# design.net
KiCad netlist of a schematic drawn in Altium Designer
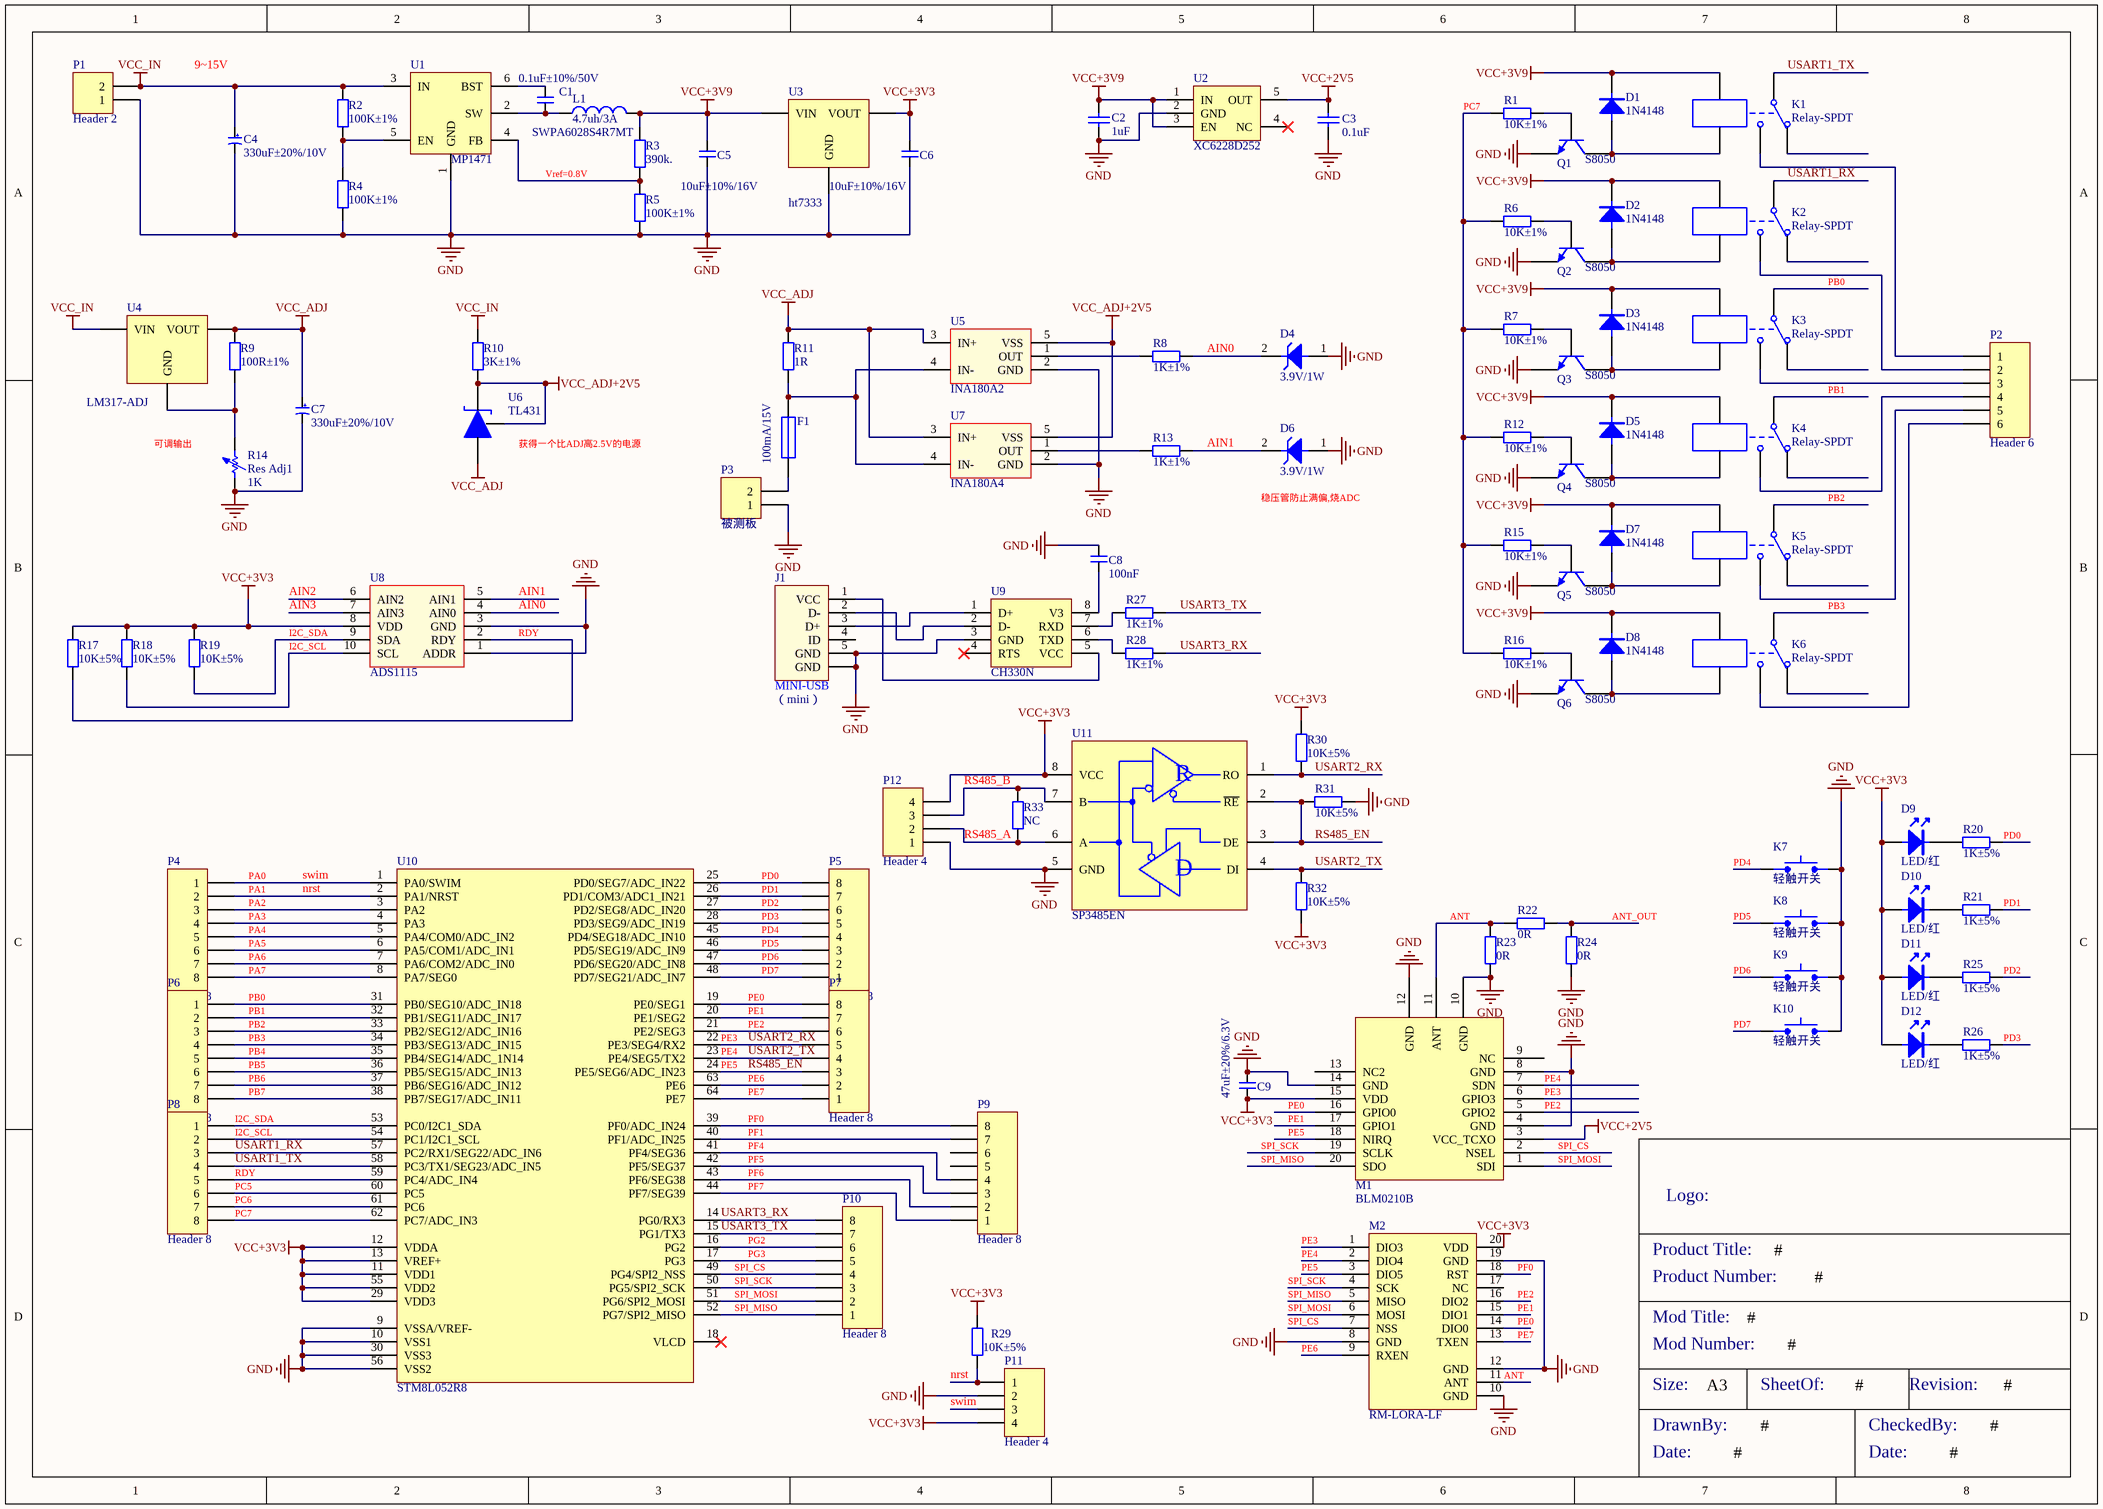
[diagram p0: 电流测试工装板.SchDoc]

(export (version "E")
  (design (tool "Eeschema 10.0.6"))
  (components
    (comp (ref "C1")
      (value "0.1uF±10%/50V")
      (footprint "c0402")
      (description "瓷片电容-0.1uF-±10%-16V-X5R-0402")
      (fields
        (field (name "PART NUMBER") "1.2.04.05.0169")
        (field (name "COMPONENTLINK1URL") "z:\\altiumdesigner\\规格书\\02原材料\\04电容\\05瓷片电容\\")
        (field (name "COMPONENTLINK2URL") "z:\\altiumdesigner\\规格书\\02原材料\\04电容\\05瓷片电容\\")
        (field (name "PUBLISHER") "徐永伟")
        (field (name "EDIT NOTE") "V1.0-创建-20161230-徐永伟")
      )
      (libsource (lib "檀木科技") (part "无极性电容"))
    )
    (comp (ref "C2")
      (value "1uF")
      (footprint "C0402")
      (description "Capacitor,Ceramic,0603-16V-X5R-104-K-YAGEO")
      (fields (field (name "MANUFACTURER") "YAGEO") (field (name "PUBLISHER") "Altium Limited"))
      (libsource (lib "*") (part "Cap"))
    )
    (comp (ref "C3")
      (value "0.1uF")
      (footprint "C0402")
      (description "Capacitor,Ceramic,0603-16V-X5R-104-K-YAGEO")
      (fields (field (name "MANUFACTURER") "YAGEO") (field (name "PUBLISHER") "Altium Limited"))
      (libsource (lib "*") (part "Cap"))
    )
    (comp (ref "C4")
      (value "330uF±20%/10V")
      (footprint "CAP_2P_2R5_D6R3H11_W")
      (description "电解电容_330uF±20%/10V_0.2R_-40~105℃_4000Hours_D6R3H11")
      (fields
        (field (name "PART NUMBER") "1.2.04.03.0001")
        (field (name "COMPONENTLINK1URL") "z:\\规格书\\02原材料\\04电容\\03铝电解电容\\常州超威电解电容RT系列.pdf")
        (field (name "PUBLISHER") "徐永伟")
        (field (name "EDIT NOTE") "V1.0-创建-20190329-徐永伟")
      )
      (libsource (lib "瑞臻信息") (part "极性电容"))
    )
    (comp (ref "C5")
      (value "10uF±10%/16V")
      (footprint "瑞臻信息:c0805")
      (description "瓷片电容-10uF-±10%-16V-X5R-0805")
      (fields
        (field (name "PART NUMBER") "1.2.04.05.0201")
        (field (name "COMPONENTLINK1URL") "z:\\altiumdesigner\\规格书\\02原材料\\04电容\\05瓷片电容\\")
        (field (name "COMPONENTLINK2URL") "z:\\altiumdesigner\\规格书\\02原材料\\04电容\\05瓷片电容\\")
        (field (name "PUBLISHER") "徐永伟")
        (field (name "EDIT NOTE") "V1.0-创建-20161230-徐永伟")
      )
      (libsource (lib "檀木科技") (part "无极性电容"))
    )
    (comp (ref "C6")
      (value "10uF±10%/16V")
      (footprint "瑞臻信息:c0805")
      (description "瓷片电容-10uF-±10%-16V-X5R-0805")
      (fields
        (field (name "PART NUMBER") "1.2.04.05.0201")
        (field (name "COMPONENTLINK1URL") "z:\\altiumdesigner\\规格书\\02原材料\\04电容\\05瓷片电容\\")
        (field (name "COMPONENTLINK2URL") "z:\\altiumdesigner\\规格书\\02原材料\\04电容\\05瓷片电容\\")
        (field (name "PUBLISHER") "徐永伟")
        (field (name "EDIT NOTE") "V1.0-创建-20161230-徐永伟")
      )
      (libsource (lib "檀木科技") (part "无极性电容"))
    )
    (comp (ref "C7")
      (value "330uF±20%/10V")
      (footprint "CAP_2P_2R5_D6R3H11_W")
      (description "电解电容_330uF±20%/10V_0.2R_-40~105℃_4000Hours_D6R3H11")
      (fields
        (field (name "PART NUMBER") "1.2.04.03.0001")
        (field (name "COMPONENTLINK1URL") "z:\\规格书\\02原材料\\04电容\\03铝电解电容\\常州超威电解电容RT系列.pdf")
        (field (name "PUBLISHER") "徐永伟")
        (field (name "EDIT NOTE") "V1.0-创建-20190329-徐永伟")
      )
      (libsource (lib "瑞臻信息") (part "极性电容"))
    )
    (comp (ref "C8")
      (value "100nF")
      (footprint "c0402")
      (description "MLCC_47uF±20%_6.3V_X5R_H1.6mm_1206")
      (fields
        (field (name "PART NUMBER") "1.2.04.05.0001")
        (field (name "COMPONENTLINK1URL") "z:\\规格书\\02原材料\\04电容\\05瓷片电容\\SAMS-S-A0000377162-1.pdf")
        (field (name "PUBLISHER") "徐永伟")
        (field (name "EDIT NOTE") "V1.0-创建-20180711-徐永伟")
      )
      (libsource (lib "瑞臻信息") (part "无极性电容"))
    )
    (comp (ref "C9")
      (value "47uF±20%/6.3V")
      (footprint "C1206")
      (description "MLCC_47uF±20%_6.3V_X5R_H1.6mm_1206")
      (fields
        (field (name "PART NUMBER") "1.2.04.05.0001")
        (field (name "COMPONENTLINK1URL") "z:\\规格书\\02原材料\\04电容\\05瓷片电容\\SAMS-S-A0000377162-1.pdf")
        (field (name "PUBLISHER") "徐永伟")
        (field (name "EDIT NOTE") "V1.0-创建-20180711-徐永伟")
      )
      (libsource (lib "瑞臻信息") (part "无极性电容"))
    )
    (comp (ref "D1")
      (value "1N4148")
      (footprint "SOD123_2P_1R6X2R7")
      (description "开关二极管_1N4148_0.3A/100V_Vf=0.5V_SOD123")
      (fields
        (field (name "PART NUMBER") "1.2.08.01.0002")
        (field (name "COMPONENTLINK1URL") "Z:\\规格书\\02原材料\\08晶体管\\01二极管\\1N4148SOD123.PDF")
        (field (name "PUBLISHER") "徐永伟")
        (field (name "EDIT NOTE") "V1.0-创建-20190815-徐永伟")
      )
      (libsource (lib "瑞臻信息") (part "普通二极管"))
    )
    (comp (ref "D2")
      (value "1N4148")
      (footprint "SOD123_2P_1R6X2R7")
      (description "开关二极管_1N4148_0.3A/100V_Vf=0.5V_SOD123")
      (fields
        (field (name "PART NUMBER") "1.2.08.01.0002")
        (field (name "COMPONENTLINK1URL") "Z:\\规格书\\02原材料\\08晶体管\\01二极管\\1N4148SOD123.PDF")
        (field (name "PUBLISHER") "徐永伟")
        (field (name "EDIT NOTE") "V1.0-创建-20190815-徐永伟")
      )
      (libsource (lib "瑞臻信息") (part "普通二极管"))
    )
    (comp (ref "D3")
      (value "1N4148")
      (footprint "SOD123_2P_1R6X2R7")
      (description "开关二极管_1N4148_0.3A/100V_Vf=0.5V_SOD123")
      (fields
        (field (name "PART NUMBER") "1.2.08.01.0002")
        (field (name "COMPONENTLINK1URL") "Z:\\规格书\\02原材料\\08晶体管\\01二极管\\1N4148SOD123.PDF")
        (field (name "PUBLISHER") "徐永伟")
        (field (name "EDIT NOTE") "V1.0-创建-20190815-徐永伟")
      )
      (libsource (lib "瑞臻信息") (part "普通二极管"))
    )
    (comp (ref "D4")
      (value "3.9V/1W")
      (footprint "LL41_2P_D2R5H5R0")
      (description "稳压二极管_ZM4730A_3.9V/1W_LL41")
      (fields
        (field (name "PART NUMBER") "1.2.08.04.0001")
        (field (name "COMPONENTLINK1URL") "Z:\\规格书\\02原材料\\08晶体管\\04稳压二极管\\ZM4730A.pdf")
        (field (name "PUBLISHER") "徐永伟")
        (field (name "EDIT NOTE") "V1.0-创建-20190815-徐永伟")
      )
      (libsource (lib "瑞臻信息") (part "齐纳二极管"))
    )
    (comp (ref "D5")
      (value "1N4148")
      (footprint "SOD123_2P_1R6X2R7")
      (description "开关二极管_1N4148_0.3A/100V_Vf=0.5V_SOD123")
      (fields
        (field (name "PART NUMBER") "1.2.08.01.0002")
        (field (name "COMPONENTLINK1URL") "Z:\\规格书\\02原材料\\08晶体管\\01二极管\\1N4148SOD123.PDF")
        (field (name "PUBLISHER") "徐永伟")
        (field (name "EDIT NOTE") "V1.0-创建-20190815-徐永伟")
      )
      (libsource (lib "瑞臻信息") (part "普通二极管"))
    )
    (comp (ref "D6")
      (value "3.9V/1W")
      (footprint "LL41_2P_D2R5H5R0")
      (description "稳压二极管_ZM4730A_3.9V/1W_LL41")
      (fields
        (field (name "PART NUMBER") "1.2.08.04.0001")
        (field (name "COMPONENTLINK1URL") "Z:\\规格书\\02原材料\\08晶体管\\04稳压二极管\\ZM4730A.pdf")
        (field (name "PUBLISHER") "徐永伟")
        (field (name "EDIT NOTE") "V1.0-创建-20190815-徐永伟")
      )
      (libsource (lib "瑞臻信息") (part "齐纳二极管"))
    )
    (comp (ref "D7")
      (value "1N4148")
      (footprint "SOD123_2P_1R6X2R7")
      (description "开关二极管_1N4148_0.3A/100V_Vf=0.5V_SOD123")
      (fields
        (field (name "PART NUMBER") "1.2.08.01.0002")
        (field (name "COMPONENTLINK1URL") "Z:\\规格书\\02原材料\\08晶体管\\01二极管\\1N4148SOD123.PDF")
        (field (name "PUBLISHER") "徐永伟")
        (field (name "EDIT NOTE") "V1.0-创建-20190815-徐永伟")
      )
      (libsource (lib "瑞臻信息") (part "普通二极管"))
    )
    (comp (ref "D8")
      (value "1N4148")
      (footprint "SOD123_2P_1R6X2R7")
      (description "开关二极管_1N4148_0.3A/100V_Vf=0.5V_SOD123")
      (fields
        (field (name "PART NUMBER") "1.2.08.01.0002")
        (field (name "COMPONENTLINK1URL") "Z:\\规格书\\02原材料\\08晶体管\\01二极管\\1N4148SOD123.PDF")
        (field (name "PUBLISHER") "徐永伟")
        (field (name "EDIT NOTE") "V1.0-创建-20190815-徐永伟")
      )
      (libsource (lib "瑞臻信息") (part "普通二极管"))
    )
    (comp (ref "D9")
      (value "LED/红")
      (footprint "PZ_1X2P_2R54_Z")
      (description "发光二极管_红色_Vf=2.3V_0603")
      (fields
        (field (name "PART NUMBER") "1.2.08.02.0002")
        (field (name "COMPONENTLINK1URL") "Z:\\规格书\\02原材料\\08晶体管\\02发光二极管\\E6C0603URAC1UDA(630nm).pdf")
        (field (name "PUBLISHER") "徐永伟")
        (field (name "EDIT NOTE") "V1.0-创建-20190815-徐永伟")
      )
      (libsource (lib "瑞臻信息") (part "单LED"))
    )
    (comp (ref "D10")
      (value "LED/红")
      (footprint "PZ_1X2P_2R54_Z")
      (description "发光二极管_红色_Vf=2.3V_0603")
      (fields
        (field (name "PART NUMBER") "1.2.08.02.0002")
        (field (name "COMPONENTLINK1URL") "Z:\\规格书\\02原材料\\08晶体管\\02发光二极管\\E6C0603URAC1UDA(630nm).pdf")
        (field (name "PUBLISHER") "徐永伟")
        (field (name "EDIT NOTE") "V1.0-创建-20190815-徐永伟")
      )
      (libsource (lib "瑞臻信息") (part "单LED"))
    )
    (comp (ref "D11")
      (value "LED/红")
      (footprint "PZ_1X2P_2R54_Z")
      (description "发光二极管_红色_Vf=2.3V_0603")
      (fields
        (field (name "PART NUMBER") "1.2.08.02.0002")
        (field (name "COMPONENTLINK1URL") "Z:\\规格书\\02原材料\\08晶体管\\02发光二极管\\E6C0603URAC1UDA(630nm).pdf")
        (field (name "PUBLISHER") "徐永伟")
        (field (name "EDIT NOTE") "V1.0-创建-20190815-徐永伟")
      )
      (libsource (lib "瑞臻信息") (part "单LED"))
    )
    (comp (ref "D12")
      (value "LED/红")
      (footprint "PZ_1X2P_2R54_Z")
      (description "发光二极管_红色_Vf=2.3V_0603")
      (fields
        (field (name "PART NUMBER") "1.2.08.02.0002")
        (field (name "COMPONENTLINK1URL") "Z:\\规格书\\02原材料\\08晶体管\\02发光二极管\\E6C0603URAC1UDA(630nm).pdf")
        (field (name "PUBLISHER") "徐永伟")
        (field (name "EDIT NOTE") "V1.0-创建-20190815-徐永伟")
      )
      (libsource (lib "瑞臻信息") (part "单LED"))
    )
    (comp (ref "F1")
      (value "100mA/15V")
      (footprint "FUSE0603")
      (description "自恢复保险丝_0.05A/15V_100A_0.5W_0.5A/1.5s_0603")
      (fields
        (field (name "PART NUMBER") "1.2.13.03.0001")
        (field (name "COMPONENTLINK1URL") "Z:\\规格书\\02原材料\\13保护器件\\03自恢复保险丝\\0.05APTC.PDF")
        (field (name "PUBLISHER") "徐永伟")
        (field (name "EDIT NOTE") "V1.0-创建-20190816-徐永伟")
      )
      (libsource (lib "瑞臻信息") (part "保险丝"))
    )
    (comp (ref "J1")
      (value "（mini）")
      (footprint "DIP_MINI_USB-1")
      (libsource (lib "瑞臻信息") (part "USB座子-2（mini）"))
    )
    (comp (ref "K1")
      (value "Relay-SPDT")
      (footprint "SRS-XXVDC-SL")
      (description "Single-Pole Dual-Throw Relay")
      (fields (field (name "PUBLISHER") "Altium Limited"))
      (libsource (lib "Miscellaneous Devices") (part "Relay-SPDT"))
    )
    (comp (ref "K2")
      (value "Relay-SPDT")
      (footprint "SRS-XXVDC-SL")
      (description "Single-Pole Dual-Throw Relay")
      (fields (field (name "PUBLISHER") "Altium Limited"))
      (libsource (lib "Miscellaneous Devices") (part "Relay-SPDT"))
    )
    (comp (ref "K3")
      (value "Relay-SPDT")
      (footprint "SRS-XXVDC-SL")
      (description "Single-Pole Dual-Throw Relay")
      (fields (field (name "PUBLISHER") "Altium Limited"))
      (libsource (lib "Miscellaneous Devices") (part "Relay-SPDT"))
    )
    (comp (ref "K4")
      (value "Relay-SPDT")
      (footprint "SRS-XXVDC-SL")
      (description "Single-Pole Dual-Throw Relay")
      (fields (field (name "PUBLISHER") "Altium Limited"))
      (libsource (lib "Miscellaneous Devices") (part "Relay-SPDT"))
    )
    (comp (ref "K5")
      (value "Relay-SPDT")
      (footprint "SRS-XXVDC-SL")
      (description "Single-Pole Dual-Throw Relay")
      (fields (field (name "PUBLISHER") "Altium Limited"))
      (libsource (lib "Miscellaneous Devices") (part "Relay-SPDT"))
    )
    (comp (ref "K6")
      (value "Relay-SPDT")
      (footprint "SRS-XXVDC-SL")
      (description "Single-Pole Dual-Throw Relay")
      (fields (field (name "PUBLISHER") "Altium Limited"))
      (libsource (lib "Miscellaneous Devices") (part "Relay-SPDT"))
    )
    (comp (ref "K7")
      (value "轻触开关")
      (footprint "PZ_1X2P_2R54_Z")
      (description "轻触开关_12Vdc/50mA_0.25mm_250gf_3.6X6.1X2.5mm_表贴SMD")
      (fields
        (field (name "PART NUMBER") "1.2.15.01.0001")
        (field (name "COMPONENTLINK1URL") "Z:\\规格书\\02原材料\\15机械开关\\01轻触按钮开关\\C118141.pdf")
        (field (name "PUBLISHER") "徐永伟")
        (field (name "EDIT NOTE") "V1.0-创建-20190825-徐永伟")
      )
      (libsource (lib "瑞臻信息") (part "2脚按键-1"))
    )
    (comp (ref "K8")
      (value "轻触开关")
      (footprint "PZ_1X2P_2R54_Z")
      (description "轻触开关_12Vdc/50mA_0.25mm_250gf_3.6X6.1X2.5mm_表贴SMD")
      (fields
        (field (name "PART NUMBER") "1.2.15.01.0001")
        (field (name "COMPONENTLINK1URL") "Z:\\规格书\\02原材料\\15机械开关\\01轻触按钮开关\\C118141.pdf")
        (field (name "PUBLISHER") "徐永伟")
        (field (name "EDIT NOTE") "V1.0-创建-20190825-徐永伟")
      )
      (libsource (lib "瑞臻信息") (part "2脚按键-1"))
    )
    (comp (ref "K9")
      (value "轻触开关")
      (footprint "PZ_1X2P_2R54_Z")
      (description "轻触开关_12Vdc/50mA_0.25mm_250gf_3.6X6.1X2.5mm_表贴SMD")
      (fields
        (field (name "PART NUMBER") "1.2.15.01.0001")
        (field (name "COMPONENTLINK1URL") "Z:\\规格书\\02原材料\\15机械开关\\01轻触按钮开关\\C118141.pdf")
        (field (name "PUBLISHER") "徐永伟")
        (field (name "EDIT NOTE") "V1.0-创建-20190825-徐永伟")
      )
      (libsource (lib "瑞臻信息") (part "2脚按键-1"))
    )
    (comp (ref "K10")
      (value "轻触开关")
      (footprint "PZ_1X2P_2R54_Z")
      (description "轻触开关_12Vdc/50mA_0.25mm_250gf_3.6X6.1X2.5mm_表贴SMD")
      (fields
        (field (name "PART NUMBER") "1.2.15.01.0001")
        (field (name "COMPONENTLINK1URL") "Z:\\规格书\\02原材料\\15机械开关\\01轻触按钮开关\\C118141.pdf")
        (field (name "PUBLISHER") "徐永伟")
        (field (name "EDIT NOTE") "V1.0-创建-20190825-徐永伟")
      )
      (libsource (lib "瑞臻信息") (part "2脚按键-1"))
    )
    (comp (ref "L1")
      (value "SWPA6028S4R7MT")
      (footprint "SMD_INC_2P_6R0X6R0")
      (description "Inductor")
      (fields (field (name "ALTIUM_VALUE") "4.7uh/3A"))
      (libsource (lib "Miscellaneous Devices") (part "Inductor"))
    )
    (comp (ref "M1")
      (value "BLM0210B")
      (footprint "FskMode_BL")
      (description "SI4463模块，不带LNA")
      (fields
        (field (name "PART NUMBER") "1.1.01.38.0002")
        (field (name "COMPONENTLINK1URL") "Z:\\规格书\\02原材料\\21电路模块\\04无线模块\\4463模块资料.rar")
        (field (name "PUBLISHER") "徐永伟")
        (field (name "EDIT NOTE") "V1.0-创建-20180709-徐永伟")
      )
      (libsource (lib "瑞臻信息") (part "SI4463_Module"))
    )
    (comp (ref "M2")
      (value "RM-LORA-LF")
      (footprint "LORA_PIN_1")
      (description "LORA模块_RM-LORA-PCB11-V2.21_430M~490M_Pout=17dBm_SMD20")
      (fields
        (field (name "PART NUMBER") "1.1.01.38.0003")
        (field (name "COMPONENTLINK1URL") "Z:\\规格书\\02原材料\\21电路模块\\04无线模块\\")
        (field (name "PUBLISHER") "徐永伟")
        (field (name "EDIT NOTE") "V1.0-创建-20180709-徐永伟")
      )
      (libsource (lib "瑞臻信息") (part "LORA_PIN_1"))
    )
    (comp (ref "P1")
      (value "Header 2")
      (footprint "HDR1X2")
      (description "Header, 2-Pin")
      (fields (field (name "PUBLISHER") "Altium Limited"))
      (libsource (lib "Miscellaneous Connectors") (part "Header 2"))
    )
    (comp (ref "P2")
      (value "Header 6")
      (footprint "HDR1X6")
      (description "Header, 6-Pin")
      (fields (field (name "PUBLISHER") "Altium Limited"))
      (libsource (lib "Miscellaneous Connectors") (part "Header 6"))
    )
    (comp (ref "P3")
      (value "被测板")
      (footprint "HDR1X2")
      (description "Header, 2-Pin")
      (fields (field (name "PUBLISHER") "Altium Limited"))
      (libsource (lib "Miscellaneous Connectors") (part "Header 2"))
    )
    (comp (ref "P4")
      (value "Header 8")
      (footprint "HDR1X8")
      (description "Header, 8-Pin")
      (fields (field (name "PUBLISHER") "Altium Limited"))
      (libsource (lib "") (part "Header 8_1"))
    )
    (comp (ref "P5")
      (value "Header 8")
      (footprint "HDR1X8")
      (description "Header, 8-Pin")
      (fields (field (name "PUBLISHER") "Altium Limited"))
      (libsource (lib "Miscellaneous Connectors") (part "Header 8"))
    )
    (comp (ref "P6")
      (value "Header 8")
      (footprint "HDR1X8")
      (description "Header, 8-Pin")
      (fields (field (name "PUBLISHER") "Altium Limited"))
      (libsource (lib "") (part "Header 8_1"))
    )
    (comp (ref "P7")
      (value "Header 8")
      (footprint "HDR1X8")
      (description "Header, 8-Pin")
      (fields (field (name "PUBLISHER") "Altium Limited"))
      (libsource (lib "Miscellaneous Connectors") (part "Header 8"))
    )
    (comp (ref "P8")
      (value "Header 8")
      (footprint "HDR1X8")
      (description "Header, 8-Pin")
      (fields (field (name "PUBLISHER") "Altium Limited"))
      (libsource (lib "") (part "Header 8_1"))
    )
    (comp (ref "P9")
      (value "Header 8")
      (footprint "HDR1X8")
      (description "Header, 8-Pin")
      (fields (field (name "PUBLISHER") "Altium Limited"))
      (libsource (lib "Miscellaneous Connectors") (part "Header 8"))
    )
    (comp (ref "P10")
      (value "Header 8")
      (footprint "HDR1X8")
      (description "Header, 8-Pin")
      (fields (field (name "PUBLISHER") "Altium Limited"))
      (libsource (lib "Miscellaneous Connectors") (part "Header 8"))
    )
    (comp (ref "P11")
      (value "Header 4")
      (footprint "HDR1X4")
      (description "Header, 4-Pin")
      (fields (field (name "PUBLISHER") "Altium Limited"))
      (libsource (lib "") (part "Header 4_1"))
    )
    (comp (ref "P12")
      (value "Header 4")
      (footprint "HDR1X4")
      (description "Header, 4-Pin")
      (fields (field (name "PUBLISHER") "Altium Limited"))
      (libsource (lib "Miscellaneous Connectors") (part "Header 4"))
    )
    (comp (ref "Q1")
      (value "S8050")
      (footprint "SOT23_3P_0R95_1R3X2R9")
      (description "三极管	_NPN_S8050_Vceo=25V_Ic=0.5A_β>50_SOT23")
      (fields
        (field (name "PART NUMBER") "1.2.08.08.0002")
        (field (name "COMPONENTLINK1URL") "Z:\\规格书\\02原材料\\08晶体管\\08三极管\\S8050_SOT23.pdf")
        (field (name "PUBLISHER") "徐永伟")
        (field (name "EDIT NOTE") "V1.0-创建-20190815-徐永伟")
      )
      (libsource (lib "瑞臻信息") (part "NPN三极管"))
    )
    (comp (ref "Q2")
      (value "S8050")
      (footprint "SOT23_3P_0R95_1R3X2R9")
      (description "三极管	_NPN_S8050_Vceo=25V_Ic=0.5A_β>50_SOT23")
      (fields
        (field (name "PART NUMBER") "1.2.08.08.0002")
        (field (name "COMPONENTLINK1URL") "Z:\\规格书\\02原材料\\08晶体管\\08三极管\\S8050_SOT23.pdf")
        (field (name "PUBLISHER") "徐永伟")
        (field (name "EDIT NOTE") "V1.0-创建-20190815-徐永伟")
      )
      (libsource (lib "瑞臻信息") (part "NPN三极管"))
    )
    (comp (ref "Q3")
      (value "S8050")
      (footprint "SOT23_3P_0R95_1R3X2R9")
      (description "三极管	_NPN_S8050_Vceo=25V_Ic=0.5A_β>50_SOT23")
      (fields
        (field (name "PART NUMBER") "1.2.08.08.0002")
        (field (name "COMPONENTLINK1URL") "Z:\\规格书\\02原材料\\08晶体管\\08三极管\\S8050_SOT23.pdf")
        (field (name "PUBLISHER") "徐永伟")
        (field (name "EDIT NOTE") "V1.0-创建-20190815-徐永伟")
      )
      (libsource (lib "瑞臻信息") (part "NPN三极管"))
    )
    (comp (ref "Q4")
      (value "S8050")
      (footprint "SOT23_3P_0R95_1R3X2R9")
      (description "三极管	_NPN_S8050_Vceo=25V_Ic=0.5A_β>50_SOT23")
      (fields
        (field (name "PART NUMBER") "1.2.08.08.0002")
        (field (name "COMPONENTLINK1URL") "Z:\\规格书\\02原材料\\08晶体管\\08三极管\\S8050_SOT23.pdf")
        (field (name "PUBLISHER") "徐永伟")
        (field (name "EDIT NOTE") "V1.0-创建-20190815-徐永伟")
      )
      (libsource (lib "瑞臻信息") (part "NPN三极管"))
    )
    (comp (ref "Q5")
      (value "S8050")
      (footprint "SOT23_3P_0R95_1R3X2R9")
      (description "三极管	_NPN_S8050_Vceo=25V_Ic=0.5A_β>50_SOT23")
      (fields
        (field (name "PART NUMBER") "1.2.08.08.0002")
        (field (name "COMPONENTLINK1URL") "Z:\\规格书\\02原材料\\08晶体管\\08三极管\\S8050_SOT23.pdf")
        (field (name "PUBLISHER") "徐永伟")
        (field (name "EDIT NOTE") "V1.0-创建-20190815-徐永伟")
      )
      (libsource (lib "瑞臻信息") (part "NPN三极管"))
    )
    (comp (ref "Q6")
      (value "S8050")
      (footprint "SOT23_3P_0R95_1R3X2R9")
      (description "三极管	_NPN_S8050_Vceo=25V_Ic=0.5A_β>50_SOT23")
      (fields
        (field (name "PART NUMBER") "1.2.08.08.0002")
        (field (name "COMPONENTLINK1URL") "Z:\\规格书\\02原材料\\08晶体管\\08三极管\\S8050_SOT23.pdf")
        (field (name "PUBLISHER") "徐永伟")
        (field (name "EDIT NOTE") "V1.0-创建-20190815-徐永伟")
      )
      (libsource (lib "瑞臻信息") (part "NPN三极管"))
    )
    (comp (ref "R1")
      (value "10K±1%")
      (footprint "R0603")
      (description "电阻_10K±1%_1/10W_0603")
      (fields
        (field (name "PART NUMBER") "1.2.03.01.0009")
        (field (name "COMPONENTLINK1URL") "z:\\规格书\\02原材料\\03电阻\\01普通电阻\\旺诠电阻.pdf")
        (field (name "创建者") "徐永伟")
      )
      (libsource (lib "瑞臻信息") (part "普通电阻"))
    )
    (comp (ref "R2")
      (value "100K±1%")
      (footprint "R0402")
      (description "贴片电阻，1K±5%，1/16W，50V，0402")
      (fields
        (field (name "PART NUMBER") "1.2.03.01.XXX1")
        (field (name "PUBLISHER") "徐永伟")
        (field (name "EDIT NOTE") "V1.0-创建-20160831-徐永伟")
      )
      (libsource (lib "檀木科技") (part "普通电阻"))
    )
    (comp (ref "R3")
      (value "390k.")
      (footprint "R0402")
      (description "电阻_510R±1%_1/16W_0402")
      (fields
        (field (name "PART NUMBER") "1.2.03.01.0019")
        (field (name "COMPONENTLINK1URL") "z:\\规格书\\02原材料\\03电阻\\01普通电阻\\厚声电阻.pdf")
        (field (name "创建者") "徐永伟")
      )
      (libsource (lib "") (part "普通电阻_1"))
    )
    (comp (ref "R4")
      (value "100K±1%")
      (footprint "R0402")
      (description "贴片电阻，1K±5%，1/16W，50V，0402")
      (fields
        (field (name "PART NUMBER") "1.2.03.01.XXX1")
        (field (name "PUBLISHER") "徐永伟")
        (field (name "EDIT NOTE") "V1.0-创建-20160831-徐永伟")
      )
      (libsource (lib "檀木科技") (part "普通电阻"))
    )
    (comp (ref "R5")
      (value "100K±1%")
      (footprint "R0402")
      (description "贴片电阻，1K±5%，1/16W，50V，0402")
      (fields
        (field (name "PART NUMBER") "1.2.03.01.XXX1")
        (field (name "PUBLISHER") "徐永伟")
        (field (name "EDIT NOTE") "V1.0-创建-20160831-徐永伟")
      )
      (libsource (lib "檀木科技") (part "普通电阻"))
    )
    (comp (ref "R6")
      (value "10K±1%")
      (footprint "R0603")
      (description "电阻_10K±1%_1/10W_0603")
      (fields
        (field (name "PART NUMBER") "1.2.03.01.0009")
        (field (name "COMPONENTLINK1URL") "z:\\规格书\\02原材料\\03电阻\\01普通电阻\\旺诠电阻.pdf")
        (field (name "创建者") "徐永伟")
      )
      (libsource (lib "瑞臻信息") (part "普通电阻"))
    )
    (comp (ref "R7")
      (value "10K±1%")
      (footprint "R0603")
      (description "电阻_10K±1%_1/10W_0603")
      (fields
        (field (name "PART NUMBER") "1.2.03.01.0009")
        (field (name "COMPONENTLINK1URL") "z:\\规格书\\02原材料\\03电阻\\01普通电阻\\旺诠电阻.pdf")
        (field (name "创建者") "徐永伟")
      )
      (libsource (lib "瑞臻信息") (part "普通电阻"))
    )
    (comp (ref "R8")
      (value "1K±1%")
      (footprint "R0603")
      (description "电阻_1K±1%_1/10W_0603")
      (fields
        (field (name "PART NUMBER") "1.2.03.01.0006")
        (field (name "COMPONENTLINK1URL") "z:\\规格书\\02原材料\\03电阻\\01普通电阻\\旺诠电阻.pdf")
        (field (name "创建者") "徐永伟")
      )
      (libsource (lib "瑞臻信息") (part "普通电阻"))
    )
    (comp (ref "R9")
      (value "100R±1%")
      (footprint "R0603")
      (description "电阻_100R±1%_1/10W_0603")
      (fields
        (field (name "PART NUMBER") "1.2.03.01.0017")
        (field (name "COMPONENTLINK1URL") "z:\\规格书\\02原材料\\03电阻\\01普通电阻\\华科电阻.pdf")
        (field (name "创建者") "徐永伟")
      )
      (libsource (lib "") (part "普通电阻_1"))
    )
    (comp (ref "R10")
      (value "3K±1%")
      (footprint "R0603")
      (description "电阻_3K±1%_1/10W_0603")
      (fields
        (field (name "PART NUMBER") "1.2.03.01.0027")
        (field (name "COMPONENTLINK1URL") "z:\\规格书\\02原材料\\03电阻\\01普通电阻\\国巨电阻.pdf")
        (field (name "创建者") "徐永伟")
      )
      (libsource (lib "") (part "普通电阻_1"))
    )
    (comp (ref "R11")
      (value "1R")
      (footprint "R0603")
      (description "电阻_3K±1%_1/10W_0603")
      (fields
        (field (name "PART NUMBER") "1.2.03.01.0027")
        (field (name "COMPONENTLINK1URL") "z:\\规格书\\02原材料\\03电阻\\01普通电阻\\国巨电阻.pdf")
        (field (name "创建者") "徐永伟")
      )
      (libsource (lib "") (part "普通电阻_1"))
    )
    (comp (ref "R12")
      (value "10K±1%")
      (footprint "R0603")
      (description "电阻_10K±1%_1/10W_0603")
      (fields
        (field (name "PART NUMBER") "1.2.03.01.0009")
        (field (name "COMPONENTLINK1URL") "z:\\规格书\\02原材料\\03电阻\\01普通电阻\\旺诠电阻.pdf")
        (field (name "创建者") "徐永伟")
      )
      (libsource (lib "瑞臻信息") (part "普通电阻"))
    )
    (comp (ref "R13")
      (value "1K±1%")
      (footprint "R0603")
      (description "电阻_1K±1%_1/10W_0603")
      (fields
        (field (name "PART NUMBER") "1.2.03.01.0006")
        (field (name "COMPONENTLINK1URL") "z:\\规格书\\02原材料\\03电阻\\01普通电阻\\旺诠电阻.pdf")
        (field (name "创建者") "徐永伟")
      )
      (libsource (lib "瑞臻信息") (part "普通电阻"))
    )
    (comp (ref "R14")
      (value "Res Adj1")
      (footprint "AXIAL-0.7")
      (description "Variable Resistor")
      (fields (field (name "ALTIUM_VALUE") "1K") (field (name "PUBLISHER") "Altium Limited"))
      (libsource (lib "Miscellaneous Devices") (part "Res Adj1"))
    )
    (comp (ref "R15")
      (value "10K±1%")
      (footprint "R0603")
      (description "电阻_10K±1%_1/10W_0603")
      (fields
        (field (name "PART NUMBER") "1.2.03.01.0009")
        (field (name "COMPONENTLINK1URL") "z:\\规格书\\02原材料\\03电阻\\01普通电阻\\旺诠电阻.pdf")
        (field (name "创建者") "徐永伟")
      )
      (libsource (lib "瑞臻信息") (part "普通电阻"))
    )
    (comp (ref "R16")
      (value "10K±1%")
      (footprint "R0603")
      (description "电阻_10K±1%_1/10W_0603")
      (fields
        (field (name "PART NUMBER") "1.2.03.01.0009")
        (field (name "COMPONENTLINK1URL") "z:\\规格书\\02原材料\\03电阻\\01普通电阻\\旺诠电阻.pdf")
        (field (name "创建者") "徐永伟")
      )
      (libsource (lib "瑞臻信息") (part "普通电阻"))
    )
    (comp (ref "R17")
      (value "10K±5%")
      (footprint "R0402")
      (description "电阻_10K±5%_1/16W_0402")
      (fields
        (field (name "PART NUMBER") "1.2.03.01.0012")
        (field (name "COMPONENTLINK1URL") "z:\\规格书\\02原材料\\03电阻\\01普通电阻\\旺诠电阻.pdf")
        (field (name "创建者") "徐永伟")
      )
      (libsource (lib "") (part "普通电阻_1"))
    )
    (comp (ref "R18")
      (value "10K±5%")
      (footprint "R0402")
      (description "电阻_10K±5%_1/16W_0402")
      (fields
        (field (name "PART NUMBER") "1.2.03.01.0012")
        (field (name "COMPONENTLINK1URL") "z:\\规格书\\02原材料\\03电阻\\01普通电阻\\旺诠电阻.pdf")
        (field (name "创建者") "徐永伟")
      )
      (libsource (lib "") (part "普通电阻_1"))
    )
    (comp (ref "R19")
      (value "10K±5%")
      (footprint "R0402")
      (description "电阻_10K±5%_1/16W_0402")
      (fields
        (field (name "PART NUMBER") "1.2.03.01.0012")
        (field (name "COMPONENTLINK1URL") "z:\\规格书\\02原材料\\03电阻\\01普通电阻\\旺诠电阻.pdf")
        (field (name "创建者") "徐永伟")
      )
      (libsource (lib "") (part "普通电阻_1"))
    )
    (comp (ref "R20")
      (value "1K±5%")
      (footprint "R0402")
      (description "电阻_1K±5%_1/16W_0402")
      (fields
        (field (name "PART NUMBER") "1.2.03.01.0014")
        (field (name "COMPONENTLINK1URL") "z:\\规格书\\02原材料\\03电阻\\01普通电阻\\旺诠电阻.pdf")
        (field (name "创建者") "徐永伟")
      )
      (libsource (lib "瑞臻信息") (part "普通电阻"))
    )
    (comp (ref "R21")
      (value "1K±5%")
      (footprint "R0402")
      (description "电阻_1K±5%_1/16W_0402")
      (fields
        (field (name "PART NUMBER") "1.2.03.01.0014")
        (field (name "COMPONENTLINK1URL") "z:\\规格书\\02原材料\\03电阻\\01普通电阻\\旺诠电阻.pdf")
        (field (name "创建者") "徐永伟")
      )
      (libsource (lib "瑞臻信息") (part "普通电阻"))
    )
    (comp (ref "R22")
      (value "0R")
      (footprint "R0603")
      (description "电阻_10K±1%_1/10W_0603")
      (fields
        (field (name "PART NUMBER") "1.2.03.01.0009")
        (field (name "COMPONENTLINK1URL") "z:\\规格书\\02原材料\\03电阻\\01普通电阻\\旺诠电阻.pdf")
        (field (name "创建者") "徐永伟")
      )
      (libsource (lib "瑞臻信息") (part "普通电阻"))
    )
    (comp (ref "R23")
      (value "0R")
      (footprint "R0603")
      (description "电阻_10K±1%_1/10W_0603")
      (fields
        (field (name "PART NUMBER") "1.2.03.01.0009")
        (field (name "COMPONENTLINK1URL") "z:\\规格书\\02原材料\\03电阻\\01普通电阻\\旺诠电阻.pdf")
        (field (name "创建者") "徐永伟")
      )
      (libsource (lib "") (part "普通电阻_1"))
    )
    (comp (ref "R24")
      (value "0R")
      (footprint "R0603")
      (description "电阻_10K±1%_1/10W_0603")
      (fields
        (field (name "PART NUMBER") "1.2.03.01.0009")
        (field (name "COMPONENTLINK1URL") "z:\\规格书\\02原材料\\03电阻\\01普通电阻\\旺诠电阻.pdf")
        (field (name "创建者") "徐永伟")
      )
      (libsource (lib "") (part "普通电阻_1"))
    )
    (comp (ref "R25")
      (value "1K±5%")
      (footprint "R0402")
      (description "电阻_1K±5%_1/16W_0402")
      (fields
        (field (name "PART NUMBER") "1.2.03.01.0014")
        (field (name "COMPONENTLINK1URL") "z:\\规格书\\02原材料\\03电阻\\01普通电阻\\旺诠电阻.pdf")
        (field (name "创建者") "徐永伟")
      )
      (libsource (lib "瑞臻信息") (part "普通电阻"))
    )
    (comp (ref "R26")
      (value "1K±5%")
      (footprint "R0402")
      (description "电阻_1K±5%_1/16W_0402")
      (fields
        (field (name "PART NUMBER") "1.2.03.01.0014")
        (field (name "COMPONENTLINK1URL") "z:\\规格书\\02原材料\\03电阻\\01普通电阻\\旺诠电阻.pdf")
        (field (name "创建者") "徐永伟")
      )
      (libsource (lib "瑞臻信息") (part "普通电阻"))
    )
    (comp (ref "R27")
      (value "1K±1%")
      (footprint "R0603")
      (description "电阻_1K±1%_1/10W_0603")
      (fields
        (field (name "PART NUMBER") "1.2.03.01.0006")
        (field (name "COMPONENTLINK1URL") "z:\\规格书\\02原材料\\03电阻\\01普通电阻\\旺诠电阻.pdf")
        (field (name "创建者") "徐永伟")
      )
      (libsource (lib "瑞臻信息") (part "普通电阻"))
    )
    (comp (ref "R28")
      (value "1K±1%")
      (footprint "R0603")
      (description "电阻_1K±1%_1/10W_0603")
      (fields
        (field (name "PART NUMBER") "1.2.03.01.0006")
        (field (name "COMPONENTLINK1URL") "z:\\规格书\\02原材料\\03电阻\\01普通电阻\\旺诠电阻.pdf")
        (field (name "创建者") "徐永伟")
      )
      (libsource (lib "瑞臻信息") (part "普通电阻"))
    )
    (comp (ref "R29")
      (value "10K±5%")
      (footprint "R0402")
      (description "电阻_10K±5%_1/16W_0402")
      (fields
        (field (name "PART NUMBER") "1.2.03.01.0012")
        (field (name "COMPONENTLINK1URL") "z:\\规格书\\02原材料\\03电阻\\01普通电阻\\旺诠电阻.pdf")
        (field (name "创建者") "徐永伟")
      )
      (libsource (lib "") (part "普通电阻_1"))
    )
    (comp (ref "R30")
      (value "10K±5%")
      (footprint "R0402")
      (description "电阻_10K±5%_1/16W_0402")
      (fields
        (field (name "PART NUMBER") "1.2.03.01.0012")
        (field (name "COMPONENTLINK1URL") "z:\\规格书\\02原材料\\03电阻\\01普通电阻\\旺诠电阻.pdf")
        (field (name "创建者") "徐永伟")
      )
      (libsource (lib "") (part "普通电阻_1"))
    )
    (comp (ref "R31")
      (value "10K±5%")
      (footprint "R0402")
      (description "电阻_10K±5%_1/16W_0402")
      (fields
        (field (name "PART NUMBER") "1.2.03.01.0012")
        (field (name "COMPONENTLINK1URL") "z:\\规格书\\02原材料\\03电阻\\01普通电阻\\旺诠电阻.pdf")
        (field (name "创建者") "徐永伟")
      )
      (libsource (lib "") (part "普通电阻_3"))
    )
    (comp (ref "R32")
      (value "10K±5%")
      (footprint "R0402")
      (description "电阻_10K±5%_1/16W_0402")
      (fields
        (field (name "PART NUMBER") "1.2.03.01.0012")
        (field (name "COMPONENTLINK1URL") "z:\\规格书\\02原材料\\03电阻\\01普通电阻\\旺诠电阻.pdf")
        (field (name "创建者") "徐永伟")
      )
      (libsource (lib "") (part "普通电阻_2"))
    )
    (comp (ref "R33")
      (value "NC")
      (footprint "R0402")
      (description "电阻_10K±5%_1/16W_0402")
      (fields
        (field (name "PART NUMBER") "1.2.03.01.0012")
        (field (name "COMPONENTLINK1URL") "z:\\规格书\\02原材料\\03电阻\\01普通电阻\\旺诠电阻.pdf")
        (field (name "创建者") "徐永伟")
      )
      (libsource (lib "") (part "普通电阻_2"))
    )
    (comp (ref "U1")
      (value "MP1471")
      (footprint "TSOT23_6P_0R95_1R6X2R9")
      (libsource (lib "4G读写器") (part "MP1471"))
    )
    (comp (ref "U2")
      (value "XC6228D252")
      (footprint "SOT23_5P_0R95_1R6X2R9")
      (description "XC6228D252_LDO稳压_500mA/2.5V_Vmax=7V_SOT23-5")
      (fields
        (field (name "PART NUMBER") "1.2.18.07.0003")
        (field (name "COMPONENTLINK1URL") "Z:\\规格书\\02原材料\\18集成电路\\17线性稳压器\\XC6228-2.5V.pdf")
        (field (name "PUBLISHER") "徐永伟")
        (field (name "EDIT NOTE") "V1.0-创建-20180709-徐永伟")
      )
      (libsource (lib "瑞臻信息") (part "XC6228"))
    )
    (comp (ref "U3")
      (value "ht7333")
      (footprint "SOT89_3P_1R5_2R5X4R5")
      (description "HT7333_LDO稳压_250mA/3.3V_Vmax=12V_SOT89")
      (fields
        (field (name "PART NUMBER") "1.2.18.07.0002")
        (field (name "COMPONENTLINK1URL") "Z:\\规格书\\02原材料\\18集成电路\\17线性稳压器\\HT7318.pdf")
        (field (name "PUBLISHER") "徐永伟")
        (field (name "EDIT NOTE") "V1.0-创建-20180709-徐永伟")
      )
      (libsource (lib "瑞臻信息") (part "HT73XX"))
    )
    (comp (ref "U4")
      (value "LM317-ADJ")
      (footprint "TO252_3P_2R3_6R2X6R7")
      (description "HT7333_LDO稳压_250mA/3.3V_Vmax=12V_SOT89")
      (fields
        (field (name "PART NUMBER") "1.2.18.07.0002")
        (field (name "COMPONENTLINK1URL") "Z:\\规格书\\02原材料\\18集成电路\\17线性稳压器\\HT7318.pdf")
        (field (name "PUBLISHER") "徐永伟")
        (field (name "EDIT NOTE") "V1.0-创建-20180709-徐永伟")
      )
      (libsource (lib "瑞臻信息") (part "HT73XX"))
    )
    (comp (ref "U5")
      (value "INA180A2")
      (footprint "SOT23_5P_0R95_1R6X2R9")
      (libsource (lib "瑞臻信息") (part "INA180A"))
    )
    (comp (ref "U6")
      (value "TL431")
      (footprint "SOT23_3P_0R95_1R3X2R9")
      (libsource (lib "瑞臻信息") (part "TL431A"))
    )
    (comp (ref "U7")
      (value "INA180A4")
      (footprint "SOT23_5P_0R95_1R6X2R9")
      (libsource (lib "瑞臻信息") (part "INA180A"))
    )
    (comp (ref "U8")
      (value "ADS1115")
      (footprint "MSOP_10P_3R0X5R0_P")
      (libsource (lib "瑞臻信息") (part "ADS1115"))
    )
    (comp (ref "U9")
      (value "CH330N")
      (footprint "SOP_8P_1R27_3R9X4R9")
      (libsource (lib "瑞臻信息") (part "CH330N"))
    )
    (comp (ref "U10")
      (value "STM8L052R8")
      (footprint "LQFP_64P_0R5_10R0X10R0")
      (description "MCU_STM8L052R8_Vin=1.8~3.6V_16MHz_Flash/64Kb_RAM/4Kb_8位_E2PROM/256B_LCD8X24_-40~85℃_LQFP64")
      (fields
        (field (name "PART NUMBER") "1.2.18.01.0001")
        (field (name "COMPONENTLINK1URL") "Z:\\规格书\\02原材料\\18集成电路\\01通用处理器\\STM8L052R8.pdf")
        (field (name "COMPONENTLINK2URL") "Z:\\规格书\\02原材料\\18集成电路\\01通用处理器\\STM8L参考手册.pdf")
        (field (name "PUBLISHER") "徐永伟")
        (field (name "EDIT NOTE") "V1.0-创建-20170105-徐永伟")
      )
      (libsource (lib "瑞臻信息") (part "STM8L052R8"))
    )
    (comp (ref "U11")
      (value "SP3485EN")
      (footprint "SOP_8P_1R27_3R9X4R9")
      (description "RS485收发器-SP3485EN-支持485收发-SOP8")
      (fields
        (field (name "PART NUMBER") "1.2.18.09.0173")
        (field (name "COMPONENTLINK1URL") "Z:\\AltiumDesigner\\规格书\\02原材料\\18集成电路\\09接口芯片\\SP3485EN.pdf")
        (field (name "PUBLISHER") "徐永伟")
        (field (name "EDIT NOTE") "V1.0-创建-20170122-徐永伟")
      )
      (libsource (lib "檀木科技") (part "SP3485"))
    )
  )
  (nets
    (net (code "1") (name "/AIN0") (class "Default")
      (node (ref "D4") (pin "2") (pinfunction "K_2") (pintype "passive"))
      (node (ref "R8") (pin "2") (pinfunction "2_2") (pintype "passive"))
      (node (ref "U8") (pin "4") (pinfunction "AIN0_4") (pintype "passive"))
    )
    (net (code "2") (name "/AIN1") (class "Default")
      (node (ref "D6") (pin "2") (pinfunction "K_2") (pintype "passive"))
      (node (ref "R13") (pin "2") (pinfunction "2_2") (pintype "passive"))
      (node (ref "U8") (pin "5") (pinfunction "AIN1_5") (pintype "passive"))
    )
    (net (code "3") (name "/AIN2") (class "Default")
      (node (ref "U8") (pin "6") (pinfunction "AIN2_6") (pintype "passive"))
    )
    (net (code "4") (name "/AIN3") (class "Default")
      (node (ref "U8") (pin "7") (pinfunction "AIN3_7") (pintype "passive"))
    )
    (net (code "5") (name "/I2C_SCL") (class "Default")
      (node (ref "P8") (pin "2") (pinfunction "2_2") (pintype "passive"))
      (node (ref "R18") (pin "1") (pinfunction "1_1") (pintype "passive"))
      (node (ref "U10") (pin "54") (pinfunction "PC1/I2C1_SCL_54") (pintype "passive"))
      (node (ref "U8") (pin "10") (pinfunction "SCL_10") (pintype "passive"))
    )
    (net (code "6") (name "/I2C_SDA") (class "Default")
      (node (ref "P8") (pin "1") (pinfunction "1_1") (pintype "passive"))
      (node (ref "R19") (pin "1") (pinfunction "1_1") (pintype "passive"))
      (node (ref "U10") (pin "53") (pinfunction "PC0/I2C1_SDA_53") (pintype "passive"))
      (node (ref "U8") (pin "9") (pinfunction "SDA_9") (pintype "passive"))
    )
    (net (code "7") (name "/PA0") (class "Default")
      (node (ref "P11") (pin "3") (pinfunction "3_3") (pintype "passive"))
      (node (ref "P4") (pin "1") (pinfunction "1_1") (pintype "passive"))
      (node (ref "U10") (pin "1") (pinfunction "PA0/SWIM_1") (pintype "passive"))
    )
    (net (code "8") (name "/PA1") (class "Default")
      (node (ref "P11") (pin "1") (pinfunction "1_1") (pintype "passive"))
      (node (ref "P4") (pin "2") (pinfunction "2_2") (pintype "passive"))
      (node (ref "R29") (pin "1") (pinfunction "1_1") (pintype "passive"))
      (node (ref "U10") (pin "2") (pinfunction "PA1/NRST_2") (pintype "passive"))
    )
    (net (code "9") (name "/PA2") (class "Default")
      (node (ref "P4") (pin "3") (pinfunction "3_3") (pintype "passive"))
      (node (ref "U10") (pin "3") (pinfunction "PA2_3") (pintype "passive"))
    )
    (net (code "10") (name "/PA3") (class "Default")
      (node (ref "P4") (pin "4") (pinfunction "4_4") (pintype "passive"))
      (node (ref "U10") (pin "4") (pinfunction "PA3_4") (pintype "passive"))
    )
    (net (code "11") (name "/PA4") (class "Default")
      (node (ref "P4") (pin "5") (pinfunction "5_5") (pintype "passive"))
      (node (ref "U10") (pin "5") (pinfunction "PA4/COM0/ADC_IN2_5") (pintype "passive"))
    )
    (net (code "12") (name "/PA5") (class "Default")
      (node (ref "P4") (pin "6") (pinfunction "6_6") (pintype "passive"))
      (node (ref "U10") (pin "6") (pinfunction "PA5/COM1/ADC_IN1_6") (pintype "passive"))
    )
    (net (code "13") (name "/PA6") (class "Default")
      (node (ref "P4") (pin "7") (pinfunction "7_7") (pintype "passive"))
      (node (ref "U10") (pin "7") (pinfunction "PA6/COM2/ADC_IN0_7") (pintype "passive"))
    )
    (net (code "14") (name "/PA7") (class "Default")
      (node (ref "P4") (pin "8") (pinfunction "8_8") (pintype "passive"))
      (node (ref "U10") (pin "8") (pinfunction "PA7/SEG0_8") (pintype "passive"))
    )
    (net (code "15") (name "/PB0") (class "Default")
      (node (ref "K3") (pin "1") (pinfunction "1_1") (pintype "passive"))
      (node (ref "P6") (pin "1") (pinfunction "1_1") (pintype "passive"))
      (node (ref "U10") (pin "31") (pinfunction "PB0/SEG10/ADC_IN18_31") (pintype "passive"))
    )
    (net (code "16") (name "/PB1") (class "Default")
      (node (ref "K4") (pin "1") (pinfunction "1_1") (pintype "passive"))
      (node (ref "P6") (pin "2") (pinfunction "2_2") (pintype "passive"))
      (node (ref "U10") (pin "32") (pinfunction "PB1/SEG11/ADC_IN17_32") (pintype "passive"))
    )
    (net (code "17") (name "/PB2") (class "Default")
      (node (ref "K5") (pin "1") (pinfunction "1_1") (pintype "passive"))
      (node (ref "P6") (pin "3") (pinfunction "3_3") (pintype "passive"))
      (node (ref "U10") (pin "33") (pinfunction "PB2/SEG12/ADC_IN16_33") (pintype "passive"))
    )
    (net (code "18") (name "/PB3") (class "Default")
      (node (ref "K6") (pin "1") (pinfunction "1_1") (pintype "passive"))
      (node (ref "P6") (pin "4") (pinfunction "4_4") (pintype "passive"))
      (node (ref "U10") (pin "34") (pinfunction "PB3/SEG13/ADC_IN15_34") (pintype "passive"))
    )
    (net (code "19") (name "/PB4") (class "Default")
      (node (ref "P6") (pin "5") (pinfunction "5_5") (pintype "passive"))
      (node (ref "U10") (pin "35") (pinfunction "PB4/SEG14/ADC_1N14_35") (pintype "passive"))
    )
    (net (code "20") (name "/PB5") (class "Default")
      (node (ref "P6") (pin "6") (pinfunction "6_6") (pintype "passive"))
      (node (ref "U10") (pin "36") (pinfunction "PB5/SEG15/ADC_IN13_36") (pintype "passive"))
    )
    (net (code "21") (name "/PB6") (class "Default")
      (node (ref "P6") (pin "7") (pinfunction "7_7") (pintype "passive"))
      (node (ref "U10") (pin "37") (pinfunction "PB6/SEG16/ADC_IN12_37") (pintype "passive"))
    )
    (net (code "22") (name "/PB7") (class "Default")
      (node (ref "P6") (pin "8") (pinfunction "8_8") (pintype "passive"))
      (node (ref "U10") (pin "38") (pinfunction "PB7/SEG17/ADC_IN11_38") (pintype "passive"))
    )
    (net (code "23") (name "/PC5") (class "Default")
      (node (ref "P8") (pin "6") (pinfunction "6_6") (pintype "passive"))
      (node (ref "U10") (pin "60") (pinfunction "PC5_60") (pintype "passive"))
    )
    (net (code "24") (name "/PC6") (class "Default")
      (node (ref "P8") (pin "7") (pinfunction "7_7") (pintype "passive"))
      (node (ref "U10") (pin "61") (pinfunction "PC6_61") (pintype "passive"))
    )
    (net (code "25") (name "/PC7") (class "Default")
      (node (ref "P8") (pin "8") (pinfunction "8_8") (pintype "passive"))
      (node (ref "R1") (pin "1") (pinfunction "1_1") (pintype "passive"))
      (node (ref "R12") (pin "1") (pinfunction "1_1") (pintype "passive"))
      (node (ref "R15") (pin "1") (pinfunction "1_1") (pintype "passive"))
      (node (ref "R16") (pin "1") (pinfunction "1_1") (pintype "passive"))
      (node (ref "R6") (pin "1") (pinfunction "1_1") (pintype "passive"))
      (node (ref "R7") (pin "1") (pinfunction "1_1") (pintype "passive"))
      (node (ref "U10") (pin "62") (pinfunction "PC7/ADC_IN3_62") (pintype "passive"))
    )
    (net (code "26") (name "/PD0") (class "Default")
      (node (ref "P5") (pin "8") (pinfunction "8_8") (pintype "passive"))
      (node (ref "R20") (pin "2") (pinfunction "2_2") (pintype "passive"))
      (node (ref "U10") (pin "25") (pinfunction "PD0/SEG7/ADC_IN22_25") (pintype "passive"))
    )
    (net (code "27") (name "/PD1") (class "Default")
      (node (ref "P5") (pin "7") (pinfunction "7_7") (pintype "passive"))
      (node (ref "R21") (pin "2") (pinfunction "2_2") (pintype "passive"))
      (node (ref "U10") (pin "26") (pinfunction "PD1/COM3/ADC1_IN21_26") (pintype "passive"))
    )
    (net (code "28") (name "/PD2") (class "Default")
      (node (ref "P5") (pin "6") (pinfunction "6_6") (pintype "passive"))
      (node (ref "R25") (pin "2") (pinfunction "2_2") (pintype "passive"))
      (node (ref "U10") (pin "27") (pinfunction "PD2/SEG8/ADC_IN20_27") (pintype "passive"))
    )
    (net (code "29") (name "/PD3") (class "Default")
      (node (ref "P5") (pin "5") (pinfunction "5_5") (pintype "passive"))
      (node (ref "R26") (pin "2") (pinfunction "2_2") (pintype "passive"))
      (node (ref "U10") (pin "28") (pinfunction "PD3/SEG9/ADC_IN19_28") (pintype "passive"))
    )
    (net (code "30") (name "/PD4") (class "Default")
      (node (ref "P5") (pin "4") (pinfunction "4_4") (pintype "passive"))
      (node (ref "U10") (pin "45") (pinfunction "PD4/SEG18/ADC_IN10_45") (pintype "passive"))
    )
    (net (code "31") (name "/PD5") (class "Default")
      (node (ref "P5") (pin "3") (pinfunction "3_3") (pintype "passive"))
      (node (ref "U10") (pin "46") (pinfunction "PD5/SEG19/ADC_IN9_46") (pintype "passive"))
    )
    (net (code "32") (name "/PD6") (class "Default")
      (node (ref "P5") (pin "2") (pinfunction "2_2") (pintype "passive"))
      (node (ref "U10") (pin "47") (pinfunction "PD6/SEG20/ADC_IN8_47") (pintype "passive"))
    )
    (net (code "33") (name "/PD7") (class "Default")
      (node (ref "P5") (pin "1") (pinfunction "1_1") (pintype "passive"))
      (node (ref "U10") (pin "48") (pinfunction "PD7/SEG21/ADC_IN7_48") (pintype "passive"))
    )
    (net (code "34") (name "/PE0") (class "Default")
      (node (ref "M1") (pin "16") (pinfunction "GPIO0_16") (pintype "passive"))
      (node (ref "M2") (pin "14") (pinfunction "DIO0_14") (pintype "passive"))
      (node (ref "P7") (pin "8") (pinfunction "8_8") (pintype "passive"))
      (node (ref "U10") (pin "19") (pinfunction "PE0/SEG1_19") (pintype "passive"))
    )
    (net (code "35") (name "/PE1") (class "Default")
      (node (ref "M1") (pin "17") (pinfunction "GPIO1_17") (pintype "passive"))
      (node (ref "M2") (pin "15") (pinfunction "DIO1_15") (pintype "passive"))
      (node (ref "P7") (pin "7") (pinfunction "7_7") (pintype "passive"))
      (node (ref "U10") (pin "20") (pinfunction "PE1/SEG2_20") (pintype "passive"))
    )
    (net (code "36") (name "/PE2") (class "Default")
      (node (ref "M1") (pin "5") (pinfunction "GPIO2_5") (pintype "passive"))
      (node (ref "M2") (pin "16") (pinfunction "DIO2_16") (pintype "passive"))
      (node (ref "P7") (pin "6") (pinfunction "6_6") (pintype "passive"))
      (node (ref "U10") (pin "21") (pinfunction "PE2/SEG3_21") (pintype "passive"))
    )
    (net (code "37") (name "/PE3") (class "Default")
      (node (ref "M1") (pin "6") (pinfunction "GPIO3_6") (pintype "passive"))
      (node (ref "M2") (pin "1") (pinfunction "DIO3_1") (pintype "passive"))
      (node (ref "P7") (pin "5") (pinfunction "5_5") (pintype "passive"))
      (node (ref "R30") (pin "1") (pinfunction "1_1") (pintype "passive"))
      (node (ref "U10") (pin "22") (pinfunction "PE3/SEG4/RX2_22") (pintype "passive"))
      (node (ref "U11") (pin "1") (pinfunction "RO_1") (pintype "passive"))
    )
    (net (code "38") (name "/PE4") (class "Default")
      (node (ref "M1") (pin "7") (pinfunction "SDN_7") (pintype "passive"))
      (node (ref "M2") (pin "2") (pinfunction "DIO4_2") (pintype "passive"))
      (node (ref "P7") (pin "4") (pinfunction "4_4") (pintype "passive"))
      (node (ref "R32") (pin "1") (pinfunction "1_1") (pintype "passive"))
      (node (ref "U10") (pin "23") (pinfunction "PE4/SEG5/TX2_23") (pintype "passive"))
      (node (ref "U11") (pin "4") (pinfunction "DI_4") (pintype "passive"))
    )
    (net (code "39") (name "/PE5") (class "Default")
      (node (ref "M1") (pin "18") (pinfunction "NIRQ_18") (pintype "passive"))
      (node (ref "M2") (pin "3") (pinfunction "DIO5_3") (pintype "passive"))
      (node (ref "P7") (pin "3") (pinfunction "3_3") (pintype "passive"))
      (node (ref "R31") (pin "2") (pinfunction "2_2") (pintype "passive"))
      (node (ref "U10") (pin "24") (pinfunction "PE5/SEG6/ADC_IN23_24") (pintype "passive"))
      (node (ref "U11") (pin "2") (pinfunction "~{RE}_2") (pintype "passive"))
      (node (ref "U11") (pin "3") (pinfunction "DE_3") (pintype "passive"))
    )
    (net (code "40") (name "/PE6") (class "Default")
      (node (ref "M2") (pin "9") (pinfunction "RXEN_9") (pintype "passive"))
      (node (ref "P7") (pin "2") (pinfunction "2_2") (pintype "passive"))
      (node (ref "U10") (pin "63") (pinfunction "PE6_63") (pintype "passive"))
    )
    (net (code "41") (name "/PE7") (class "Default")
      (node (ref "M2") (pin "13") (pinfunction "TXEN_13") (pintype "passive"))
      (node (ref "P7") (pin "1") (pinfunction "1_1") (pintype "passive"))
      (node (ref "U10") (pin "64") (pinfunction "PE7_64") (pintype "passive"))
    )
    (net (code "42") (name "/PF0") (class "Default")
      (node (ref "M2") (pin "18") (pinfunction "RST_18") (pintype "passive"))
      (node (ref "P9") (pin "8") (pinfunction "8_8") (pintype "passive"))
      (node (ref "U10") (pin "39") (pinfunction "PF0/ADC_IN24_39") (pintype "passive"))
    )
    (net (code "43") (name "/PF1") (class "Default")
      (node (ref "P9") (pin "7") (pinfunction "7_7") (pintype "passive"))
      (node (ref "U10") (pin "40") (pinfunction "PF1/ADC_IN25_40") (pintype "passive"))
    )
    (net (code "44") (name "/PF4") (class "Default")
      (node (ref "P9") (pin "4") (pinfunction "4_4") (pintype "passive"))
      (node (ref "U10") (pin "41") (pinfunction "PF4/SEG36_41") (pintype "passive"))
    )
    (net (code "45") (name "/PF5") (class "Default")
      (node (ref "P9") (pin "3") (pinfunction "3_3") (pintype "passive"))
      (node (ref "U10") (pin "42") (pinfunction "PF5/SEG37_42") (pintype "passive"))
    )
    (net (code "46") (name "/PF6") (class "Default")
      (node (ref "P9") (pin "2") (pinfunction "2_2") (pintype "passive"))
      (node (ref "U10") (pin "43") (pinfunction "PF6/SEG38_43") (pintype "passive"))
    )
    (net (code "47") (name "/PF7") (class "Default")
      (node (ref "P9") (pin "1") (pinfunction "1_1") (pintype "passive"))
      (node (ref "U10") (pin "44") (pinfunction "PF7/SEG39_44") (pintype "passive"))
    )
    (net (code "48") (name "/PG2") (class "Default")
      (node (ref "P10") (pin "6") (pinfunction "6_6") (pintype "passive"))
      (node (ref "U10") (pin "16") (pinfunction "PG2_16") (pintype "passive"))
    )
    (net (code "49") (name "/PG3") (class "Default")
      (node (ref "P10") (pin "5") (pinfunction "5_5") (pintype "passive"))
      (node (ref "U10") (pin "17") (pinfunction "PG3_17") (pintype "passive"))
    )
    (net (code "50") (name "/RDY") (class "Default")
      (node (ref "P8") (pin "5") (pinfunction "5_5") (pintype "passive"))
      (node (ref "R17") (pin "1") (pinfunction "1_1") (pintype "passive"))
      (node (ref "U10") (pin "59") (pinfunction "PC4/ADC_IN4_59") (pintype "passive"))
      (node (ref "U8") (pin "2") (pinfunction "RDY_2") (pintype "passive"))
    )
    (net (code "51") (name "/RS485_A") (class "Default")
      (node (ref "P12") (pin "2") (pinfunction "2_2") (pintype "passive"))
      (node (ref "R33") (pin "2") (pinfunction "2_2") (pintype "passive"))
      (node (ref "U11") (pin "6") (pinfunction "A_6") (pintype "passive"))
    )
    (net (code "52") (name "/RS485_B") (class "Default")
      (node (ref "P12") (pin "3") (pinfunction "3_3") (pintype "passive"))
      (node (ref "R33") (pin "1") (pinfunction "1_1") (pintype "passive"))
      (node (ref "U11") (pin "7") (pinfunction "B_7") (pintype "passive"))
    )
    (net (code "53") (name "/SPI_CS") (class "Default")
      (node (ref "M1") (pin "2") (pinfunction "NSEL_2") (pintype "passive"))
      (node (ref "M2") (pin "7") (pinfunction "NSS_7") (pintype "passive"))
      (node (ref "P10") (pin "4") (pinfunction "4_4") (pintype "passive"))
      (node (ref "U10") (pin "49") (pinfunction "PG4/SPI2_NSS_49") (pintype "passive"))
    )
    (net (code "54") (name "/SPI_MISO") (class "Default")
      (node (ref "M1") (pin "20") (pinfunction "SDO_20") (pintype "passive"))
      (node (ref "M2") (pin "5") (pinfunction "MISO_5") (pintype "passive"))
      (node (ref "P10") (pin "1") (pinfunction "1_1") (pintype "passive"))
      (node (ref "U10") (pin "52") (pinfunction "PG7/SPI2_MISO_52") (pintype "passive"))
    )
    (net (code "55") (name "/SPI_MOSI") (class "Default")
      (node (ref "M1") (pin "1") (pinfunction "SDI_1") (pintype "passive"))
      (node (ref "M2") (pin "6") (pinfunction "MOSI_6") (pintype "passive"))
      (node (ref "P10") (pin "2") (pinfunction "2_2") (pintype "passive"))
      (node (ref "U10") (pin "51") (pinfunction "PG6/SPI2_MOSI_51") (pintype "passive"))
    )
    (net (code "56") (name "/SPI_SCK") (class "Default")
      (node (ref "M1") (pin "19") (pinfunction "SCLK_19") (pintype "passive"))
      (node (ref "M2") (pin "4") (pinfunction "SCK_4") (pintype "passive"))
      (node (ref "P10") (pin "3") (pinfunction "3_3") (pintype "passive"))
      (node (ref "U10") (pin "50") (pinfunction "PG5/SPI2_SCK_50") (pintype "passive"))
    )
    (net (code "57") (name "/USART1_RX") (class "Default")
      (node (ref "K2") (pin "1") (pinfunction "1_1") (pintype "passive"))
      (node (ref "P8") (pin "3") (pinfunction "3_3") (pintype "passive"))
      (node (ref "U10") (pin "57") (pinfunction "PC2/RX1/SEG22/ADC_IN6_57") (pintype "passive"))
    )
    (net (code "58") (name "/USART1_TX") (class "Default")
      (node (ref "K1") (pin "1") (pinfunction "1_1") (pintype "passive"))
      (node (ref "P8") (pin "4") (pinfunction "4_4") (pintype "passive"))
      (node (ref "U10") (pin "58") (pinfunction "PC3/TX1/SEG23/ADC_IN5_58") (pintype "passive"))
    )
    (net (code "59") (name "/USART3_RX") (class "Default")
      (node (ref "P10") (pin "8") (pinfunction "8_8") (pintype "passive"))
      (node (ref "R28") (pin "2") (pinfunction "2_2") (pintype "passive"))
      (node (ref "U10") (pin "14") (pinfunction "PG0/RX3_14") (pintype "passive"))
    )
    (net (code "60") (name "/USART3_TX") (class "Default")
      (node (ref "P10") (pin "7") (pinfunction "7_7") (pintype "passive"))
      (node (ref "R27") (pin "2") (pinfunction "2_2") (pintype "passive"))
      (node (ref "U10") (pin "15") (pinfunction "PG1/TX3_15") (pintype "passive"))
    )
    (net (code "61") (name "GND") (class "Default")
      (node (ref "C2") (pin "1") (pinfunction "1_1") (pintype "passive"))
      (node (ref "C3") (pin "1") (pinfunction "1_1") (pintype "passive"))
      (node (ref "C4") (pin "2") (pinfunction "2_2") (pintype "passive"))
      (node (ref "C5") (pin "1") (pinfunction "1_1") (pintype "passive"))
      (node (ref "C6") (pin "1") (pinfunction "1_1") (pintype "passive"))
      (node (ref "C7") (pin "2") (pinfunction "2_2") (pintype "passive"))
      (node (ref "C8") (pin "2") (pinfunction "2_2") (pintype "passive"))
      (node (ref "C9") (pin "2") (pinfunction "2_2") (pintype "passive"))
      (node (ref "D4") (pin "1") (pinfunction "A_1") (pintype "passive"))
      (node (ref "D6") (pin "1") (pinfunction "A_1") (pintype "passive"))
      (node (ref "J1") (pin "5") (pinfunction "GND_5") (pintype "passive"))
      (node (ref "J1") (pin "A") (pinfunction "GND_A") (pintype "passive"))
      (node (ref "K10") (pin "2") (pinfunction "2_2") (pintype "passive"))
      (node (ref "K7") (pin "2") (pinfunction "2_2") (pintype "passive"))
      (node (ref "K8") (pin "2") (pinfunction "2_2") (pintype "passive"))
      (node (ref "K9") (pin "2") (pinfunction "2_2") (pintype "passive"))
      (node (ref "M1") (pin "10") (pinfunction "GND_10") (pintype "passive"))
      (node (ref "M1") (pin "12") (pinfunction "GND_12") (pintype "passive"))
      (node (ref "M1") (pin "14") (pinfunction "GND_14") (pintype "passive"))
      (node (ref "M1") (pin "4") (pinfunction "GND_4") (pintype "passive"))
      (node (ref "M1") (pin "8") (pinfunction "GND_8") (pintype "passive"))
      (node (ref "M2") (pin "10") (pinfunction "GND_10") (pintype "passive"))
      (node (ref "M2") (pin "12") (pinfunction "GND_12") (pintype "passive"))
      (node (ref "M2") (pin "19") (pinfunction "GND_19") (pintype "passive"))
      (node (ref "M2") (pin "8") (pinfunction "GND_8") (pintype "passive"))
      (node (ref "P1") (pin "1") (pinfunction "1_1") (pintype "passive"))
      (node (ref "P11") (pin "2") (pinfunction "2_2") (pintype "passive"))
      (node (ref "P12") (pin "1") (pinfunction "1_1") (pintype "passive"))
      (node (ref "P3") (pin "1") (pinfunction "1_1") (pintype "passive"))
      (node (ref "Q1") (pin "2") (pinfunction "E_2") (pintype "passive"))
      (node (ref "Q2") (pin "2") (pinfunction "E_2") (pintype "passive"))
      (node (ref "Q3") (pin "2") (pinfunction "E_2") (pintype "passive"))
      (node (ref "Q4") (pin "2") (pinfunction "E_2") (pintype "passive"))
      (node (ref "Q5") (pin "2") (pinfunction "E_2") (pintype "passive"))
      (node (ref "Q6") (pin "2") (pinfunction "E_2") (pintype "passive"))
      (node (ref "R14") (pin "1") (pinfunction "1_1") (pintype "passive"))
      (node (ref "R23") (pin "1") (pinfunction "1_1") (pintype "passive"))
      (node (ref "R24") (pin "1") (pinfunction "1_1") (pintype "passive"))
      (node (ref "R31") (pin "1") (pinfunction "1_1") (pintype "passive"))
      (node (ref "R4") (pin "1") (pinfunction "1_1") (pintype "passive"))
      (node (ref "R5") (pin "1") (pinfunction "1_1") (pintype "passive"))
      (node (ref "U1") (pin "1") (pinfunction "GND_1") (pintype "passive"))
      (node (ref "U10") (pin "10") (pinfunction "VSS1_10") (pintype "passive"))
      (node (ref "U10") (pin "30") (pinfunction "VSS3_30") (pintype "passive"))
      (node (ref "U10") (pin "56") (pinfunction "VSS2_56") (pintype "passive"))
      (node (ref "U10") (pin "9") (pinfunction "VSSA/VREF-_9") (pintype "passive"))
      (node (ref "U11") (pin "5") (pinfunction "GND_5") (pintype "passive"))
      (node (ref "U2") (pin "2") (pinfunction "GND_2") (pintype "passive"))
      (node (ref "U3") (pin "1") (pinfunction "GND_1") (pintype "passive"))
      (node (ref "U5") (pin "2") (pinfunction "GND_2") (pintype "passive"))
      (node (ref "U7") (pin "2") (pinfunction "GND_2") (pintype "passive"))
      (node (ref "U8") (pin "1") (pinfunction "ADDR_1") (pintype "passive"))
      (node (ref "U8") (pin "3") (pinfunction "GND_3") (pintype "passive"))
      (node (ref "U9") (pin "3") (pinfunction "GND_3") (pintype "passive"))
    )
    (net (code "62") (name "Net-(D1-A)") (class "Default")
      (node (ref "D1") (pin "1") (pinfunction "A_1") (pintype "passive"))
      (node (ref "K1") (pin "5") (pinfunction "5_5") (pintype "passive"))
      (node (ref "Q1") (pin "3") (pinfunction "C_3") (pintype "passive"))
    )
    (net (code "63") (name "Net-(D2-A)") (class "Default")
      (node (ref "D2") (pin "1") (pinfunction "A_1") (pintype "passive"))
      (node (ref "K2") (pin "5") (pinfunction "5_5") (pintype "passive"))
      (node (ref "Q2") (pin "3") (pinfunction "C_3") (pintype "passive"))
    )
    (net (code "64") (name "Net-(D3-A)") (class "Default")
      (node (ref "D3") (pin "1") (pinfunction "A_1") (pintype "passive"))
      (node (ref "K3") (pin "5") (pinfunction "5_5") (pintype "passive"))
      (node (ref "Q3") (pin "3") (pinfunction "C_3") (pintype "passive"))
    )
    (net (code "65") (name "Net-(D5-A)") (class "Default")
      (node (ref "D5") (pin "1") (pinfunction "A_1") (pintype "passive"))
      (node (ref "K4") (pin "5") (pinfunction "5_5") (pintype "passive"))
      (node (ref "Q4") (pin "3") (pinfunction "C_3") (pintype "passive"))
    )
    (net (code "66") (name "Net-(D7-A)") (class "Default")
      (node (ref "D7") (pin "1") (pinfunction "A_1") (pintype "passive"))
      (node (ref "K5") (pin "5") (pinfunction "5_5") (pintype "passive"))
      (node (ref "Q5") (pin "3") (pinfunction "C_3") (pintype "passive"))
    )
    (net (code "67") (name "Net-(D8-A)") (class "Default")
      (node (ref "D8") (pin "1") (pinfunction "A_1") (pintype "passive"))
      (node (ref "K6") (pin "5") (pinfunction "5_5") (pintype "passive"))
      (node (ref "Q6") (pin "3") (pinfunction "C_3") (pintype "passive"))
    )
    (net (code "68") (name "Net-(D9-K)") (class "Default")
      (node (ref "D9") (pin "2") (pinfunction "K_2") (pintype "passive"))
      (node (ref "R20") (pin "1") (pinfunction "1_1") (pintype "passive"))
    )
    (net (code "69") (name "Net-(D10-K)") (class "Default")
      (node (ref "D10") (pin "2") (pinfunction "K_2") (pintype "passive"))
      (node (ref "R21") (pin "1") (pinfunction "1_1") (pintype "passive"))
    )
    (net (code "70") (name "Net-(D11-K)") (class "Default")
      (node (ref "D11") (pin "2") (pinfunction "K_2") (pintype "passive"))
      (node (ref "R25") (pin "1") (pinfunction "1_1") (pintype "passive"))
    )
    (net (code "71") (name "Net-(D12-K)") (class "Default")
      (node (ref "D12") (pin "2") (pinfunction "K_2") (pintype "passive"))
      (node (ref "R26") (pin "1") (pinfunction "1_1") (pintype "passive"))
    )
    (net (code "72") (name "Net-(F1-Pad1)") (class "Default")
      (node (ref "F1") (pin "1") (pinfunction "1_1") (pintype "passive"))
      (node (ref "P3") (pin "2") (pinfunction "2_2") (pintype "passive"))
    )
    (net (code "73") (name "Net-(J1-D+)") (class "Default")
      (node (ref "J1") (pin "3") (pinfunction "D+_3") (pintype "passive"))
      (node (ref "U9") (pin "1") (pinfunction "D+_1") (pintype "passive"))
    )
    (net (code "74") (name "Net-(J1-D-)") (class "Default")
      (node (ref "J1") (pin "2") (pinfunction "D-_2") (pintype "passive"))
      (node (ref "U9") (pin "2") (pinfunction "D-_2") (pintype "passive"))
    )
    (net (code "75") (name "Net-(J1-VCC)") (class "Default")
      (node (ref "J1") (pin "1") (pinfunction "VCC_1") (pintype "passive"))
      (node (ref "U9") (pin "5") (pinfunction "VCC_5") (pintype "passive"))
    )
    (net (code "76") (name "Net-(K1-Pad3)") (class "Default")
      (node (ref "K1") (pin "3") (pinfunction "3_3") (pintype "passive"))
      (node (ref "P2") (pin "1") (pinfunction "1_1") (pintype "passive"))
    )
    (net (code "77") (name "Net-(K2-Pad3)") (class "Default")
      (node (ref "K2") (pin "3") (pinfunction "3_3") (pintype "passive"))
      (node (ref "P2") (pin "2") (pinfunction "2_2") (pintype "passive"))
    )
    (net (code "78") (name "Net-(K3-Pad3)") (class "Default")
      (node (ref "K3") (pin "3") (pinfunction "3_3") (pintype "passive"))
      (node (ref "P2") (pin "3") (pinfunction "3_3") (pintype "passive"))
    )
    (net (code "79") (name "Net-(K4-Pad3)") (class "Default")
      (node (ref "K4") (pin "3") (pinfunction "3_3") (pintype "passive"))
      (node (ref "P2") (pin "4") (pinfunction "4_4") (pintype "passive"))
    )
    (net (code "80") (name "Net-(K5-Pad3)") (class "Default")
      (node (ref "K5") (pin "3") (pinfunction "3_3") (pintype "passive"))
      (node (ref "P2") (pin "5") (pinfunction "5_5") (pintype "passive"))
    )
    (net (code "81") (name "Net-(K6-Pad3)") (class "Default")
      (node (ref "K6") (pin "3") (pinfunction "3_3") (pintype "passive"))
      (node (ref "P2") (pin "6") (pinfunction "6_6") (pintype "passive"))
    )
    (net (code "82") (name "Net-(M1-ANT)") (class "Default")
      (node (ref "M1") (pin "11") (pinfunction "ANT_11") (pintype "passive"))
      (node (ref "R22") (pin "1") (pinfunction "1_1") (pintype "passive"))
      (node (ref "R23") (pin "2") (pinfunction "2_2") (pintype "passive"))
    )
    (net (code "83") (name "Net-(Q1-B)") (class "Default")
      (node (ref "Q1") (pin "1") (pinfunction "B_1") (pintype "passive"))
      (node (ref "R1") (pin "2") (pinfunction "2_2") (pintype "passive"))
    )
    (net (code "84") (name "Net-(Q2-B)") (class "Default")
      (node (ref "Q2") (pin "1") (pinfunction "B_1") (pintype "passive"))
      (node (ref "R6") (pin "2") (pinfunction "2_2") (pintype "passive"))
    )
    (net (code "85") (name "Net-(Q3-B)") (class "Default")
      (node (ref "Q3") (pin "1") (pinfunction "B_1") (pintype "passive"))
      (node (ref "R7") (pin "2") (pinfunction "2_2") (pintype "passive"))
    )
    (net (code "86") (name "Net-(Q4-B)") (class "Default")
      (node (ref "Q4") (pin "1") (pinfunction "B_1") (pintype "passive"))
      (node (ref "R12") (pin "2") (pinfunction "2_2") (pintype "passive"))
    )
    (net (code "87") (name "Net-(Q5-B)") (class "Default")
      (node (ref "Q5") (pin "1") (pinfunction "B_1") (pintype "passive"))
      (node (ref "R15") (pin "2") (pinfunction "2_2") (pintype "passive"))
    )
    (net (code "88") (name "Net-(Q6-B)") (class "Default")
      (node (ref "Q6") (pin "1") (pinfunction "B_1") (pintype "passive"))
      (node (ref "R16") (pin "2") (pinfunction "2_2") (pintype "passive"))
    )
    (net (code "89") (name "Net-(R22-Pad2)") (class "Default")
      (node (ref "R22") (pin "2") (pinfunction "2_2") (pintype "passive"))
      (node (ref "R24") (pin "2") (pinfunction "2_2") (pintype "passive"))
    )
    (net (code "90") (name "Net-(U1-BST)") (class "Default")
      (node (ref "C1") (pin "2") (pinfunction "2_2") (pintype "passive"))
      (node (ref "U1") (pin "6") (pinfunction "BST_6") (pintype "passive"))
    )
    (net (code "91") (name "Net-(U1-EN)") (class "Default")
      (node (ref "R2") (pin "1") (pinfunction "1_1") (pintype "passive"))
      (node (ref "R4") (pin "2") (pinfunction "2_2") (pintype "passive"))
      (node (ref "U1") (pin "5") (pinfunction "EN_5") (pintype "passive"))
    )
    (net (code "92") (name "Net-(U1-FB)") (class "Default")
      (node (ref "R3") (pin "1") (pinfunction "1_1") (pintype "passive"))
      (node (ref "R5") (pin "2") (pinfunction "2_2") (pintype "passive"))
      (node (ref "U1") (pin "4") (pinfunction "FB_4") (pintype "passive"))
    )
    (net (code "93") (name "Net-(U1-SW)") (class "Default")
      (node (ref "C1") (pin "1") (pinfunction "1_1") (pintype "passive"))
      (node (ref "L1") (pin "1") (pinfunction "1_1") (pintype "passive"))
      (node (ref "U1") (pin "2") (pinfunction "SW_2") (pintype "passive"))
    )
    (net (code "94") (name "Net-(U4-GND)") (class "Default")
      (node (ref "R14") (pin "2") (pinfunction "2_2") (pintype "passive"))
      (node (ref "R9") (pin "1") (pinfunction "1_1") (pintype "passive"))
      (node (ref "U4") (pin "1") (pinfunction "GND_1") (pintype "passive"))
    )
    (net (code "95") (name "Net-(U5-IN-)") (class "Default")
      (node (ref "F1") (pin "2") (pinfunction "2_2") (pintype "passive"))
      (node (ref "R11") (pin "1") (pinfunction "1_1") (pintype "passive"))
      (node (ref "U5") (pin "4") (pinfunction "IN-_4") (pintype "passive"))
      (node (ref "U7") (pin "4") (pinfunction "IN-_4") (pintype "passive"))
    )
    (net (code "96") (name "Net-(U5-OUT)") (class "Default")
      (node (ref "R8") (pin "1") (pinfunction "1_1") (pintype "passive"))
      (node (ref "U5") (pin "1") (pinfunction "OUT_1") (pintype "passive"))
    )
    (net (code "97") (name "Net-(U7-OUT)") (class "Default")
      (node (ref "R13") (pin "1") (pinfunction "1_1") (pintype "passive"))
      (node (ref "U7") (pin "1") (pinfunction "OUT_1") (pintype "passive"))
    )
    (net (code "98") (name "Net-(U9-RXD)") (class "Default")
      (node (ref "R27") (pin "1") (pinfunction "1_1") (pintype "passive"))
      (node (ref "U9") (pin "7") (pinfunction "RXD_7") (pintype "passive"))
    )
    (net (code "99") (name "Net-(U9-TXD)") (class "Default")
      (node (ref "R28") (pin "1") (pinfunction "1_1") (pintype "passive"))
      (node (ref "U9") (pin "6") (pinfunction "TXD_6") (pintype "passive"))
    )
    (net (code "100") (name "Net-(U9-V3)") (class "Default")
      (node (ref "C8") (pin "1") (pinfunction "1_1") (pintype "passive"))
      (node (ref "U9") (pin "8") (pinfunction "V3_8") (pintype "passive"))
    )
    (net (code "101") (name "VCC+2V5") (class "Default")
      (node (ref "C3") (pin "2") (pinfunction "2_2") (pintype "passive"))
      (node (ref "M1") (pin "3") (pinfunction "VCC_TCXO_3") (pintype "passive"))
      (node (ref "U2") (pin "5") (pinfunction "OUT_5") (pintype "passive"))
    )
    (net (code "102") (name "VCC+3V3") (class "Default")
      (node (ref "C6") (pin "2") (pinfunction "2_2") (pintype "passive"))
      (node (ref "C9") (pin "1") (pinfunction "1_1") (pintype "passive"))
      (node (ref "D10") (pin "1") (pinfunction "A_1") (pintype "passive"))
      (node (ref "D11") (pin "1") (pinfunction "A_1") (pintype "passive"))
      (node (ref "D12") (pin "1") (pinfunction "A_1") (pintype "passive"))
      (node (ref "D9") (pin "1") (pinfunction "A_1") (pintype "passive"))
      (node (ref "M1") (pin "15") (pinfunction "VDD_15") (pintype "passive"))
      (node (ref "M2") (pin "20") (pinfunction "VDD_20") (pintype "passive"))
      (node (ref "P11") (pin "4") (pinfunction "4_4") (pintype "passive"))
      (node (ref "P12") (pin "4") (pinfunction "4_4") (pintype "passive"))
      (node (ref "R17") (pin "2") (pinfunction "2_2") (pintype "passive"))
      (node (ref "R18") (pin "2") (pinfunction "2_2") (pintype "passive"))
      (node (ref "R19") (pin "2") (pinfunction "2_2") (pintype "passive"))
      (node (ref "R29") (pin "2") (pinfunction "2_2") (pintype "passive"))
      (node (ref "R30") (pin "2") (pinfunction "2_2") (pintype "passive"))
      (node (ref "R32") (pin "2") (pinfunction "2_2") (pintype "passive"))
      (node (ref "U10") (pin "11") (pinfunction "VDD1_11") (pintype "passive"))
      (node (ref "U10") (pin "12") (pinfunction "VDDA_12") (pintype "passive"))
      (node (ref "U10") (pin "13") (pinfunction "VREF+_13") (pintype "passive"))
      (node (ref "U10") (pin "29") (pinfunction "VDD3_29") (pintype "passive"))
      (node (ref "U10") (pin "55") (pinfunction "VDD2_55") (pintype "passive"))
      (node (ref "U11") (pin "8") (pinfunction "VCC_8") (pintype "passive"))
      (node (ref "U3") (pin "3") (pinfunction "VOUT_3") (pintype "passive"))
      (node (ref "U8") (pin "8") (pinfunction "VDD_8") (pintype "passive"))
    )
    (net (code "103") (name "VCC+3V9") (class "Default")
      (node (ref "C2") (pin "2") (pinfunction "2_2") (pintype "passive"))
      (node (ref "C5") (pin "2") (pinfunction "2_2") (pintype "passive"))
      (node (ref "D1") (pin "2") (pinfunction "K_2") (pintype "passive"))
      (node (ref "D2") (pin "2") (pinfunction "K_2") (pintype "passive"))
      (node (ref "D3") (pin "2") (pinfunction "K_2") (pintype "passive"))
      (node (ref "D5") (pin "2") (pinfunction "K_2") (pintype "passive"))
      (node (ref "D7") (pin "2") (pinfunction "K_2") (pintype "passive"))
      (node (ref "D8") (pin "2") (pinfunction "K_2") (pintype "passive"))
      (node (ref "K1") (pin "4") (pinfunction "4_4") (pintype "passive"))
      (node (ref "K2") (pin "4") (pinfunction "4_4") (pintype "passive"))
      (node (ref "K3") (pin "4") (pinfunction "4_4") (pintype "passive"))
      (node (ref "K4") (pin "4") (pinfunction "4_4") (pintype "passive"))
      (node (ref "K5") (pin "4") (pinfunction "4_4") (pintype "passive"))
      (node (ref "K6") (pin "4") (pinfunction "4_4") (pintype "passive"))
      (node (ref "L1") (pin "2") (pinfunction "2_2") (pintype "passive"))
      (node (ref "R3") (pin "2") (pinfunction "2_2") (pintype "passive"))
      (node (ref "U2") (pin "1") (pinfunction "IN_1") (pintype "passive"))
      (node (ref "U2") (pin "3") (pinfunction "EN_3") (pintype "passive"))
      (node (ref "U3") (pin "2") (pinfunction "VIN_2") (pintype "passive"))
    )
    (net (code "104") (name "VCC_ADJ") (class "Default")
      (node (ref "C7") (pin "1") (pinfunction "1_1") (pintype "passive"))
      (node (ref "R11") (pin "2") (pinfunction "2_2") (pintype "passive"))
      (node (ref "R9") (pin "2") (pinfunction "2_2") (pintype "passive"))
      (node (ref "U4") (pin "3") (pinfunction "VOUT_3") (pintype "passive"))
      (node (ref "U5") (pin "3") (pinfunction "IN+_3") (pintype "passive"))
      (node (ref "U6") (pin "3") (pinfunction "A_3") (pintype "passive"))
      (node (ref "U7") (pin "3") (pinfunction "IN+_3") (pintype "passive"))
    )
    (net (code "105") (name "VCC_ADJ+2V5") (class "Default")
      (node (ref "R10") (pin "1") (pinfunction "1_1") (pintype "passive"))
      (node (ref "U5") (pin "5") (pinfunction "VSS_5") (pintype "passive"))
      (node (ref "U6") (pin "1") (pinfunction "K_1") (pintype "passive"))
      (node (ref "U6") (pin "2") (pinfunction "REF_2") (pintype "passive"))
      (node (ref "U7") (pin "5") (pinfunction "VSS_5") (pintype "passive"))
    )
    (net (code "106") (name "VCC_IN") (class "Default")
      (node (ref "C4") (pin "1") (pinfunction "1_1") (pintype "passive"))
      (node (ref "P1") (pin "2") (pinfunction "2_2") (pintype "passive"))
      (node (ref "R10") (pin "2") (pinfunction "2_2") (pintype "passive"))
      (node (ref "R2") (pin "2") (pinfunction "2_2") (pintype "passive"))
      (node (ref "U1") (pin "3") (pinfunction "IN_3") (pintype "passive"))
      (node (ref "U4") (pin "2") (pinfunction "VIN_2") (pintype "passive"))
    )
    (net (code "107") (name "unconnected-(J1-ID-Pad4)") (class "Default")
      (node (ref "J1") (pin "4") (pinfunction "ID_4") (pintype "passive"))
    )
    (net (code "108") (name "unconnected-(K1-Pad2)") (class "Default")
      (node (ref "K1") (pin "2") (pinfunction "2_2") (pintype "passive"))
    )
    (net (code "109") (name "unconnected-(K2-Pad2)") (class "Default")
      (node (ref "K2") (pin "2") (pinfunction "2_2") (pintype "passive"))
    )
    (net (code "110") (name "unconnected-(K3-Pad2)") (class "Default")
      (node (ref "K3") (pin "2") (pinfunction "2_2") (pintype "passive"))
    )
    (net (code "111") (name "unconnected-(K4-Pad2)") (class "Default")
      (node (ref "K4") (pin "2") (pinfunction "2_2") (pintype "passive"))
    )
    (net (code "112") (name "unconnected-(K5-Pad2)") (class "Default")
      (node (ref "K5") (pin "2") (pinfunction "2_2") (pintype "passive"))
    )
    (net (code "113") (name "unconnected-(K6-Pad2)") (class "Default")
      (node (ref "K6") (pin "2") (pinfunction "2_2") (pintype "passive"))
    )
    (net (code "114") (name "unconnected-(K7-Pad1)") (class "Default")
      (node (ref "K7") (pin "1") (pinfunction "1_1") (pintype "passive"))
    )
    (net (code "115") (name "unconnected-(K8-Pad1)") (class "Default")
      (node (ref "K8") (pin "1") (pinfunction "1_1") (pintype "passive"))
    )
    (net (code "116") (name "unconnected-(K9-Pad1)") (class "Default")
      (node (ref "K9") (pin "1") (pinfunction "1_1") (pintype "passive"))
    )
    (net (code "117") (name "unconnected-(K10-Pad1)") (class "Default")
      (node (ref "K10") (pin "1") (pinfunction "1_1") (pintype "passive"))
    )
    (net (code "118") (name "unconnected-(M1-NC-Pad9)") (class "Default")
      (node (ref "M1") (pin "9") (pinfunction "NC_9") (pintype "passive"))
    )
    (net (code "119") (name "unconnected-(M1-NC2-Pad13)") (class "Default")
      (node (ref "M1") (pin "13") (pinfunction "NC2_13") (pintype "passive"))
    )
    (net (code "120") (name "unconnected-(M2-ANT-Pad11)") (class "Default")
      (node (ref "M2") (pin "11") (pinfunction "ANT_11") (pintype "passive"))
    )
    (net (code "121") (name "unconnected-(M2-NC-Pad17)") (class "Default")
      (node (ref "M2") (pin "17") (pinfunction "NC_17") (pintype "passive"))
    )
    (net (code "122") (name "unconnected-(P9-Pad5)") (class "Default")
      (node (ref "P9") (pin "5") (pinfunction "5_5") (pintype "passive"))
    )
    (net (code "123") (name "unconnected-(P9-Pad6)") (class "Default")
      (node (ref "P9") (pin "6") (pinfunction "6_6") (pintype "passive"))
    )
    (net (code "124") (name "unconnected-(U2-NC-Pad4)") (class "Default")
      (node (ref "U2") (pin "4") (pinfunction "NC_4") (pintype "passive+no_connect"))
    )
    (net (code "125") (name "unconnected-(U9-RTS-Pad4)") (class "Default")
      (node (ref "U9") (pin "4") (pinfunction "RTS_4") (pintype "passive+no_connect"))
    )
    (net (code "126") (name "unconnected-(U10-VLCD-Pad18)") (class "Default")
      (node (ref "U10") (pin "18") (pinfunction "VLCD_18") (pintype "passive+no_connect"))
    )
  )
)
